# ComputeCalculator.net
KiCad netlist of a schematic drawn in EAGLE
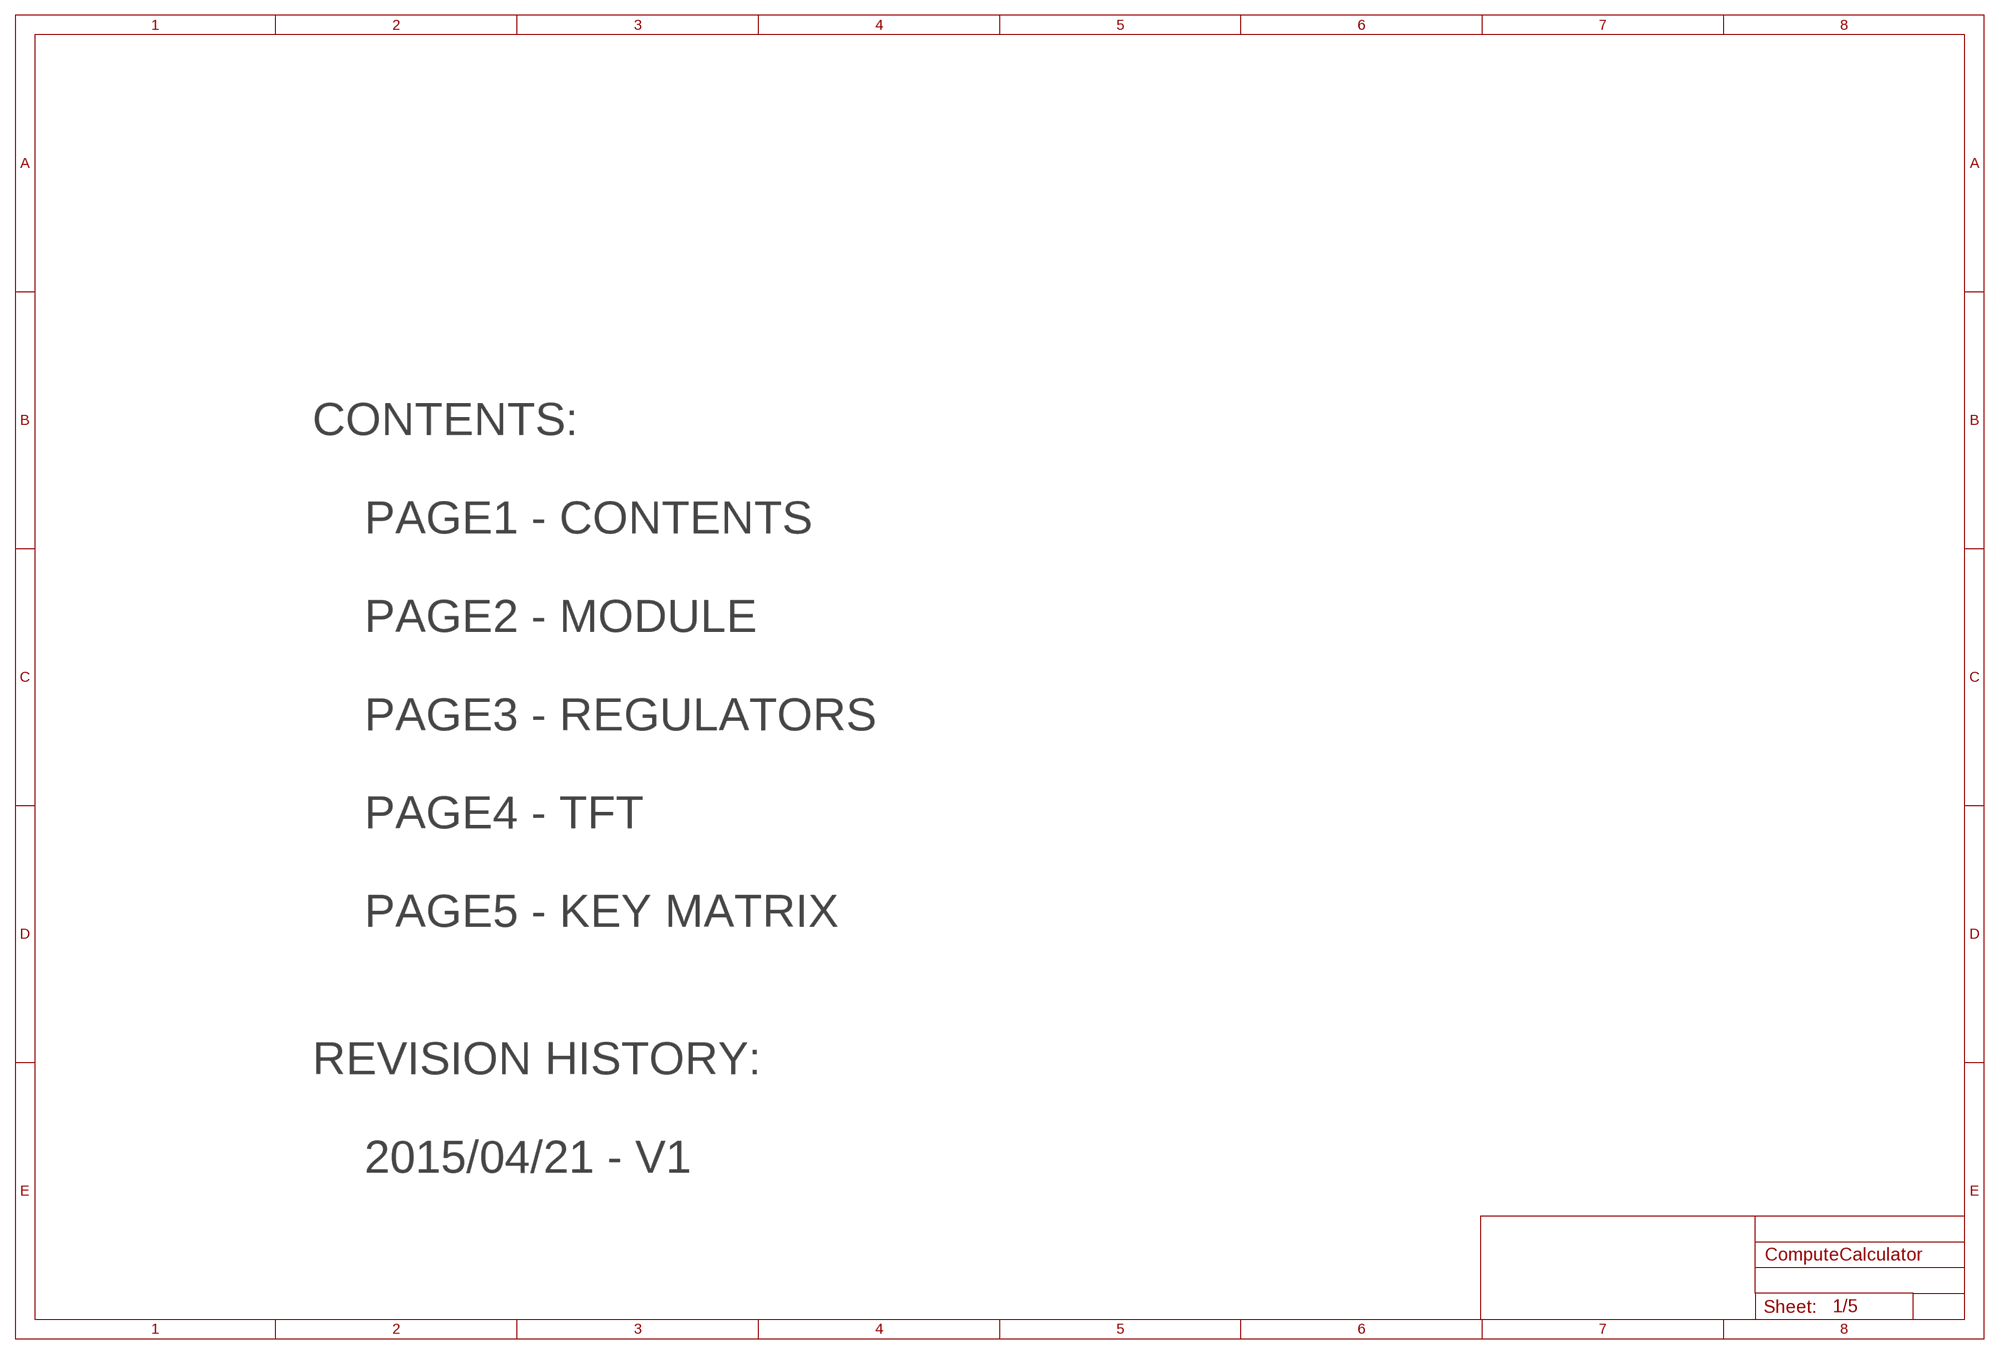
[diagram p0: schematic, sheet 1]
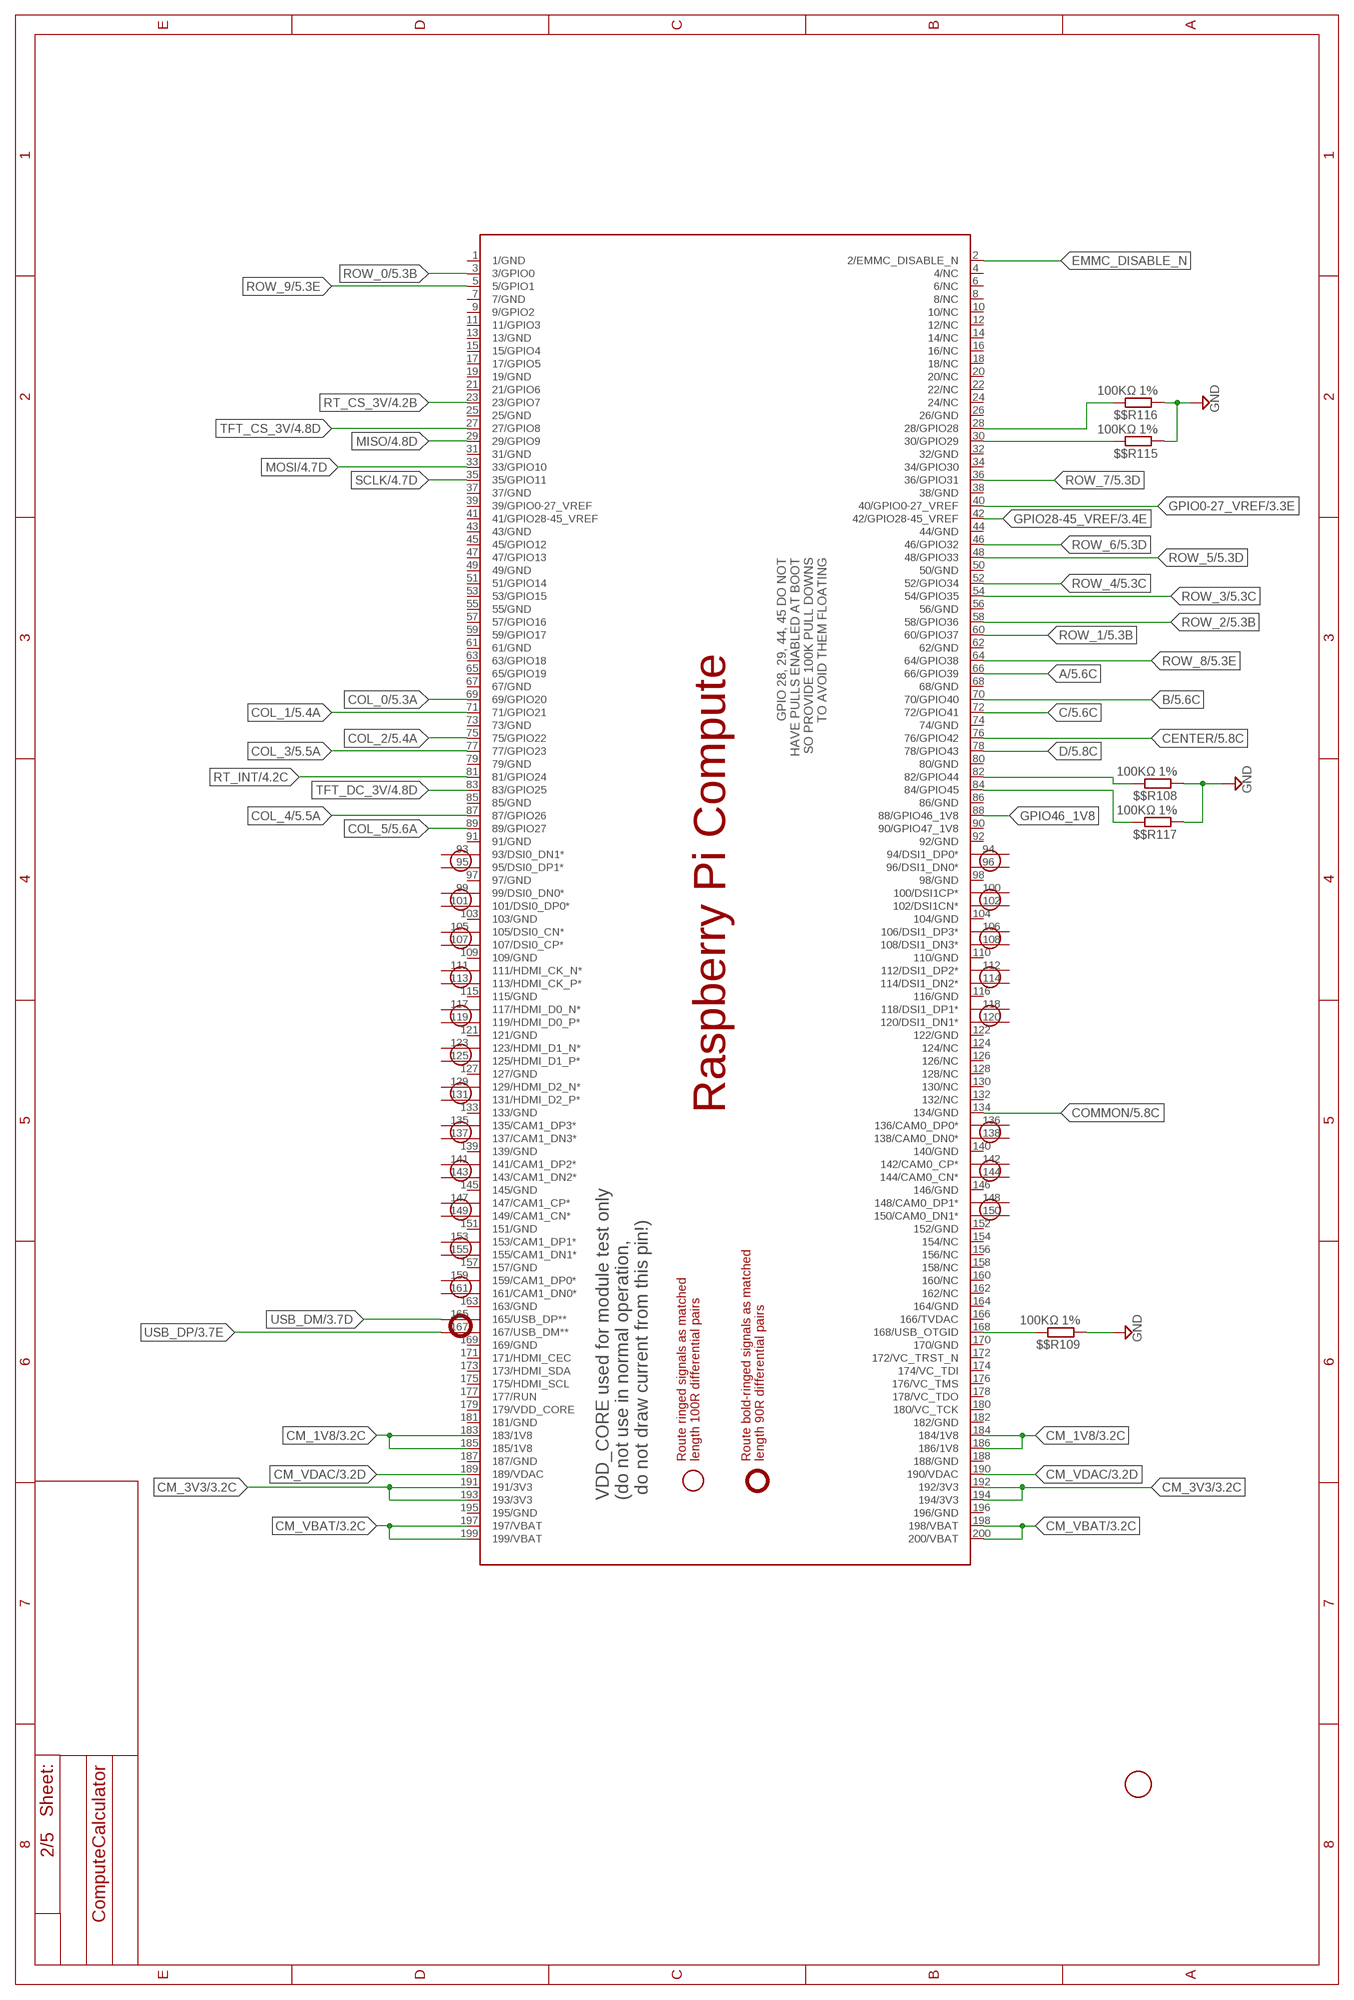
[diagram p1: schematic, sheet 2]
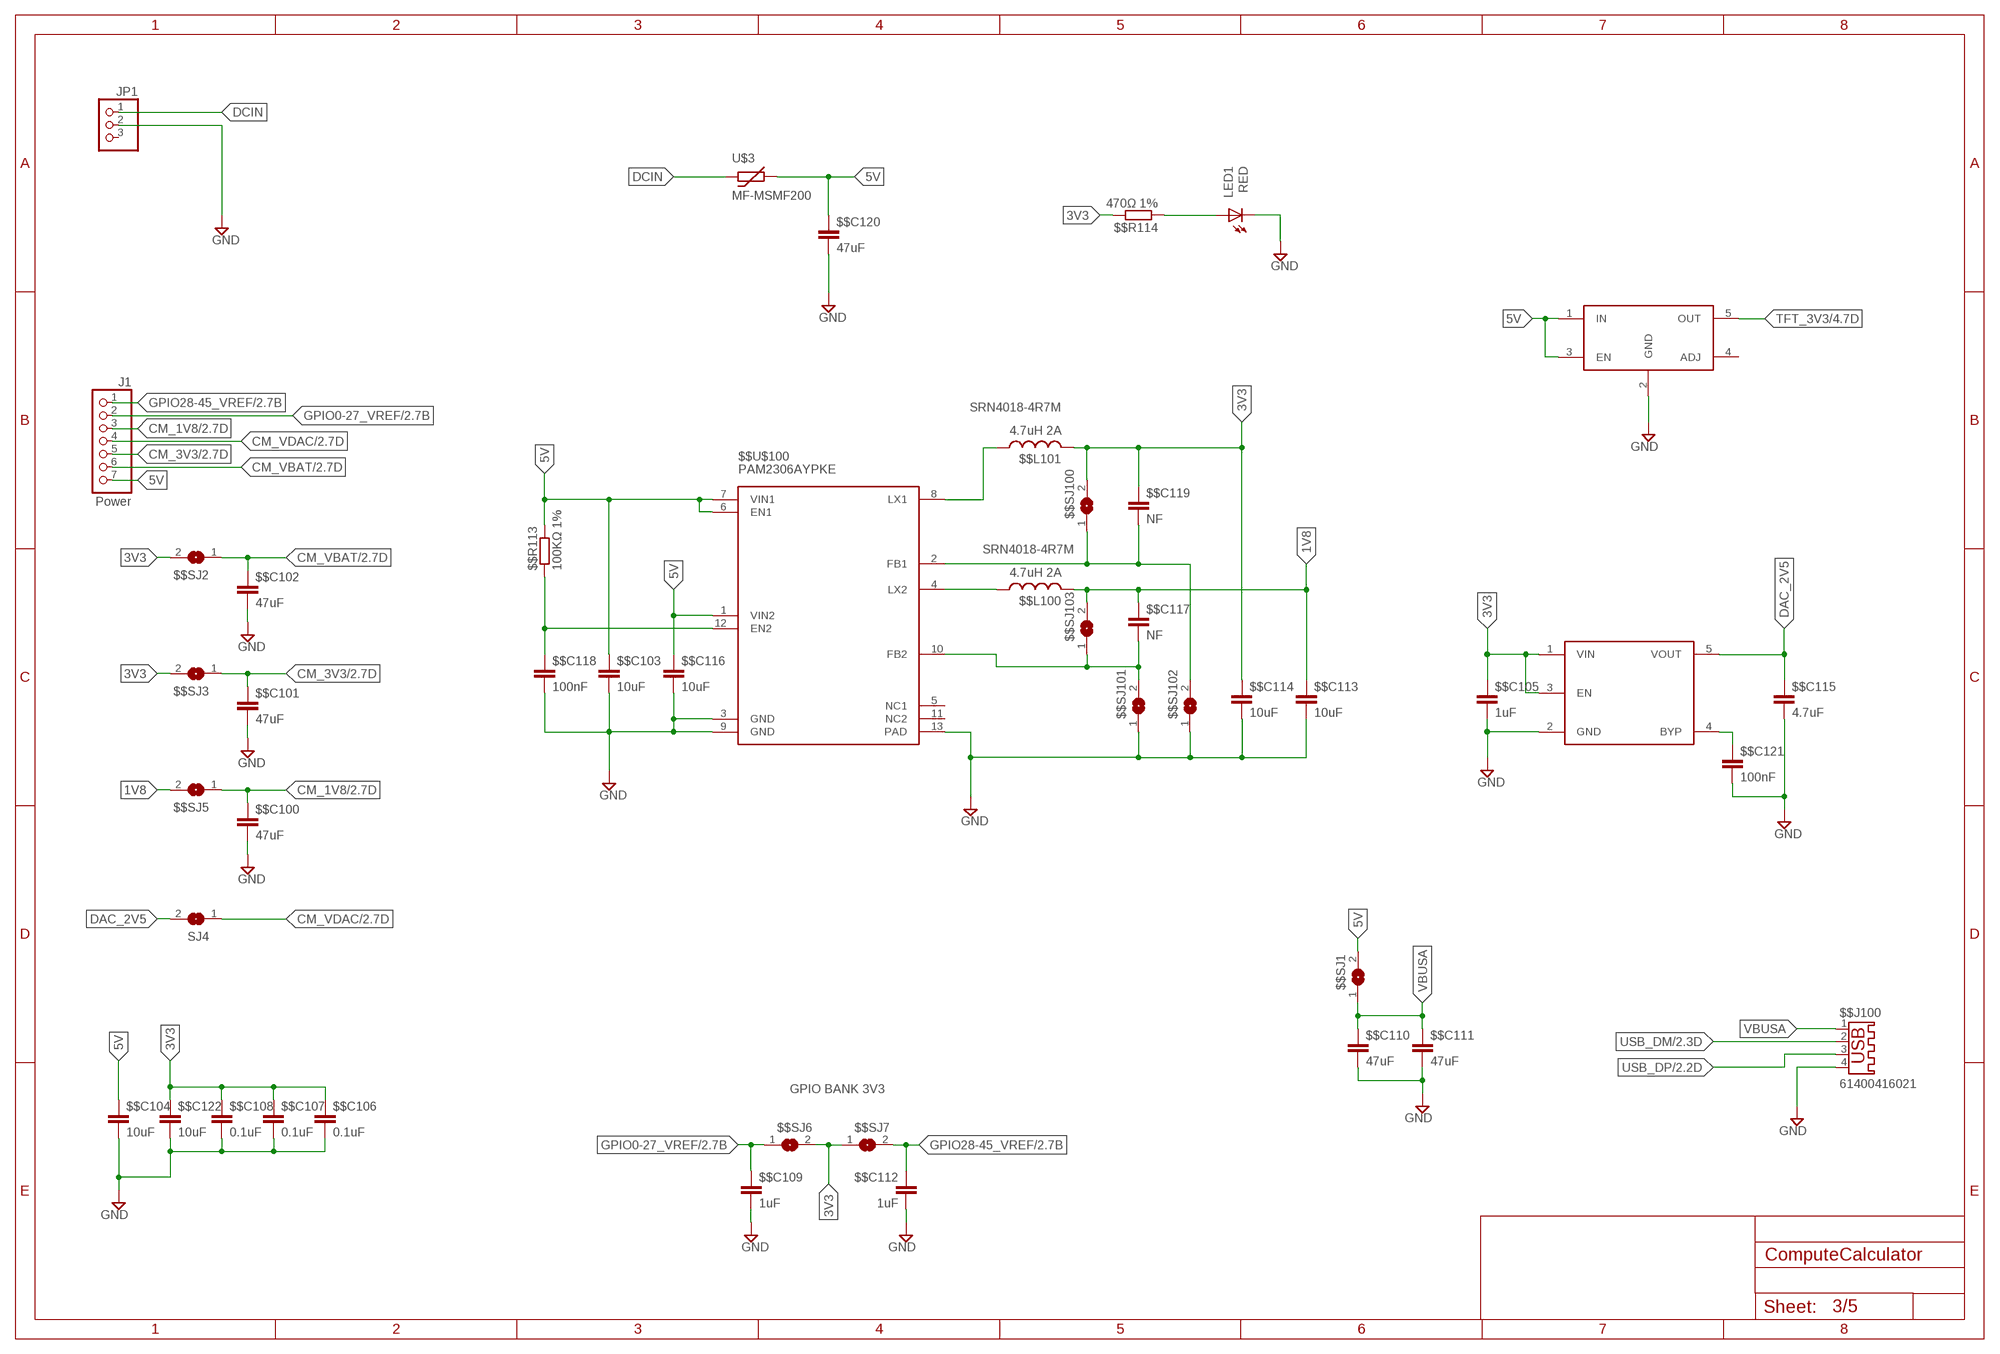
[diagram p2: schematic, sheet 3]
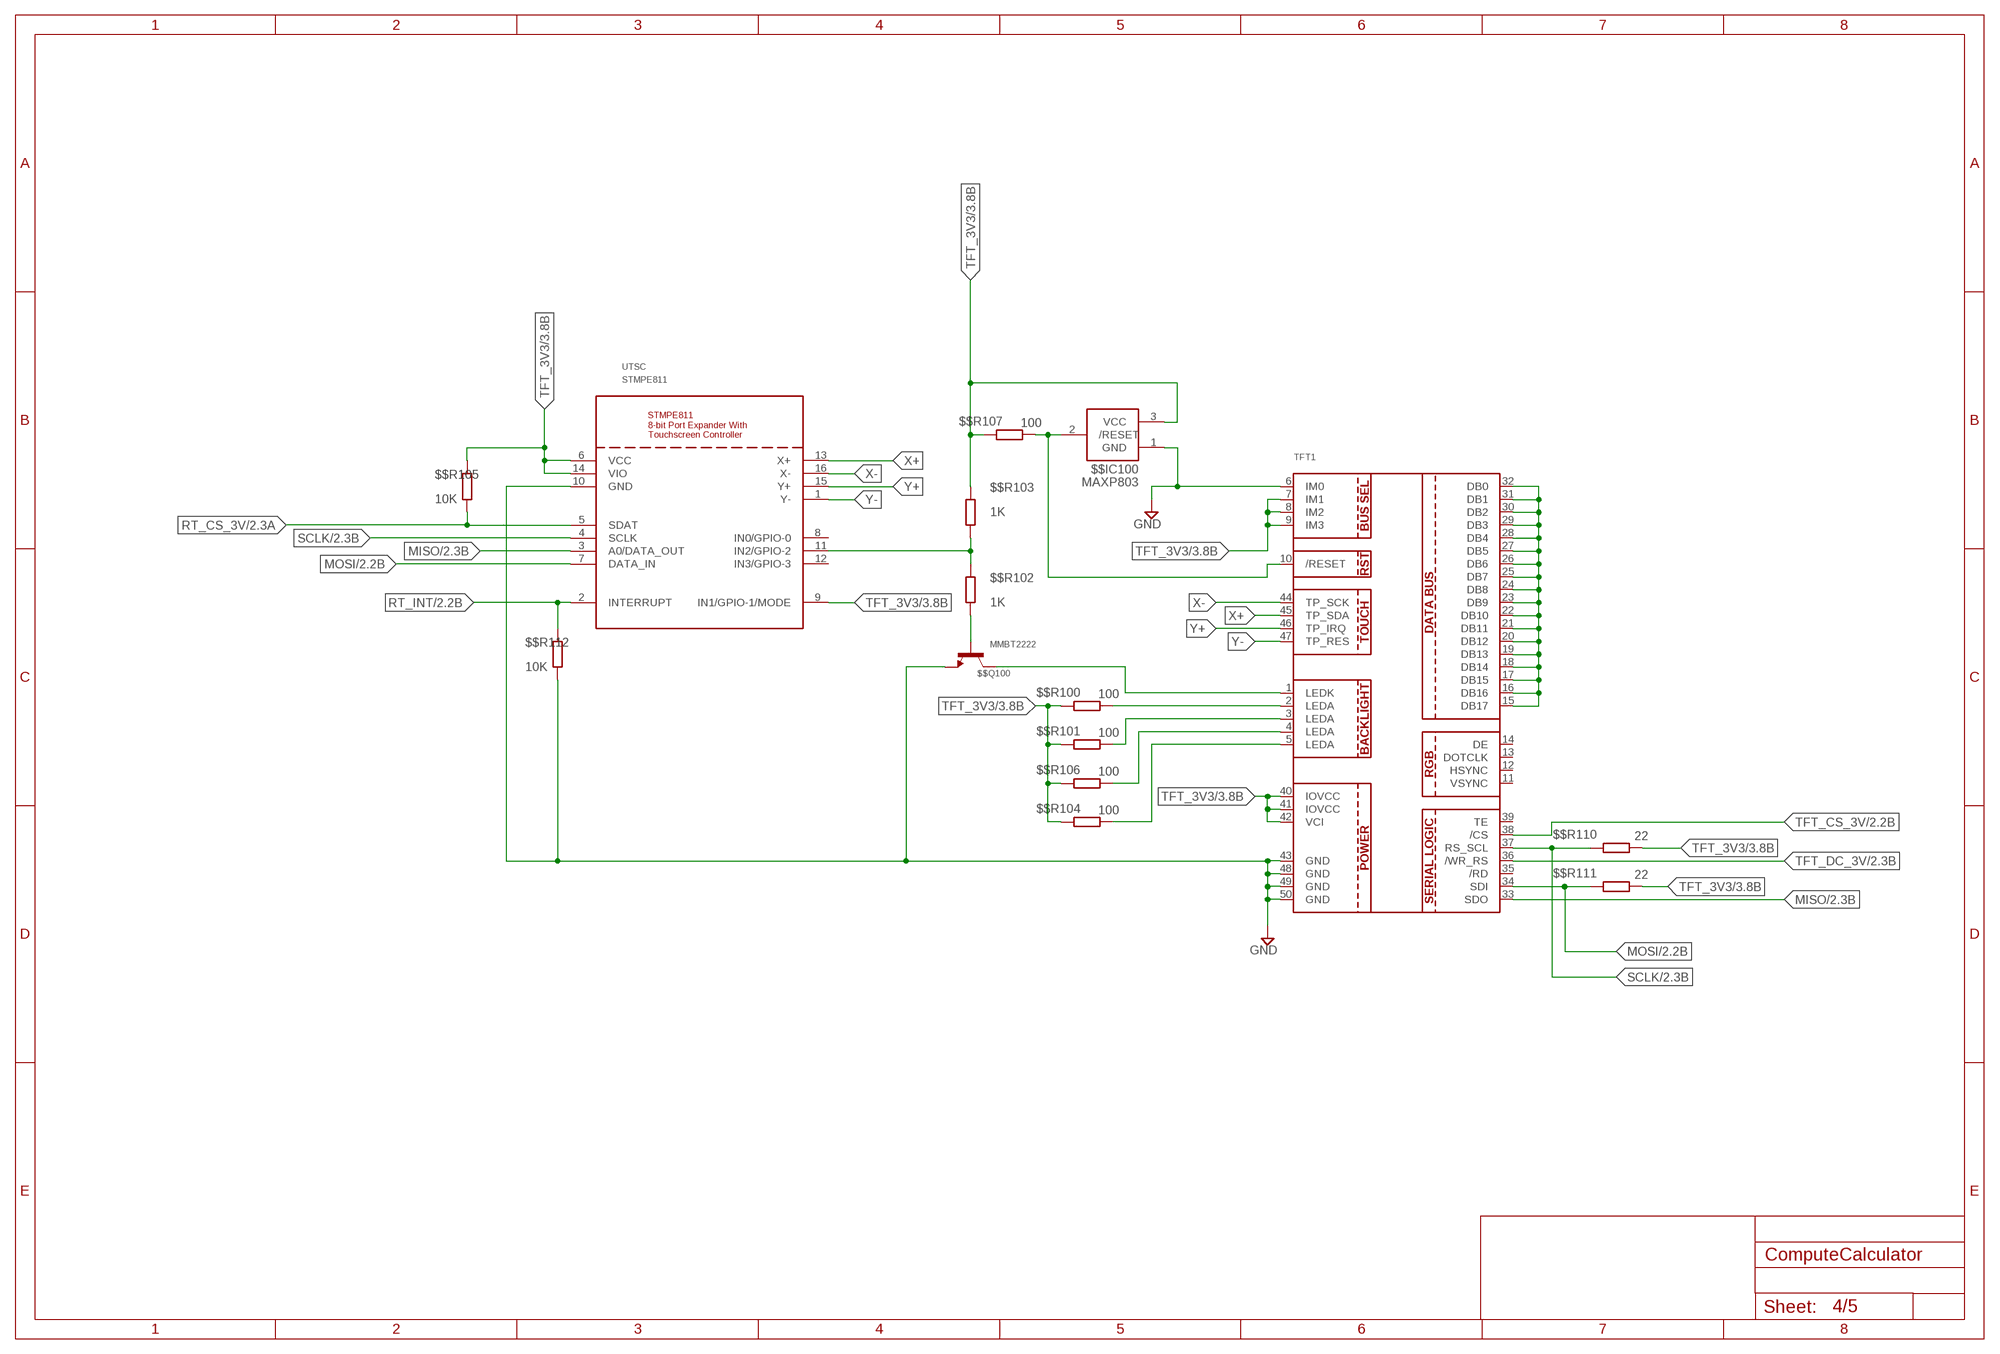
[diagram p3: schematic, sheet 4]
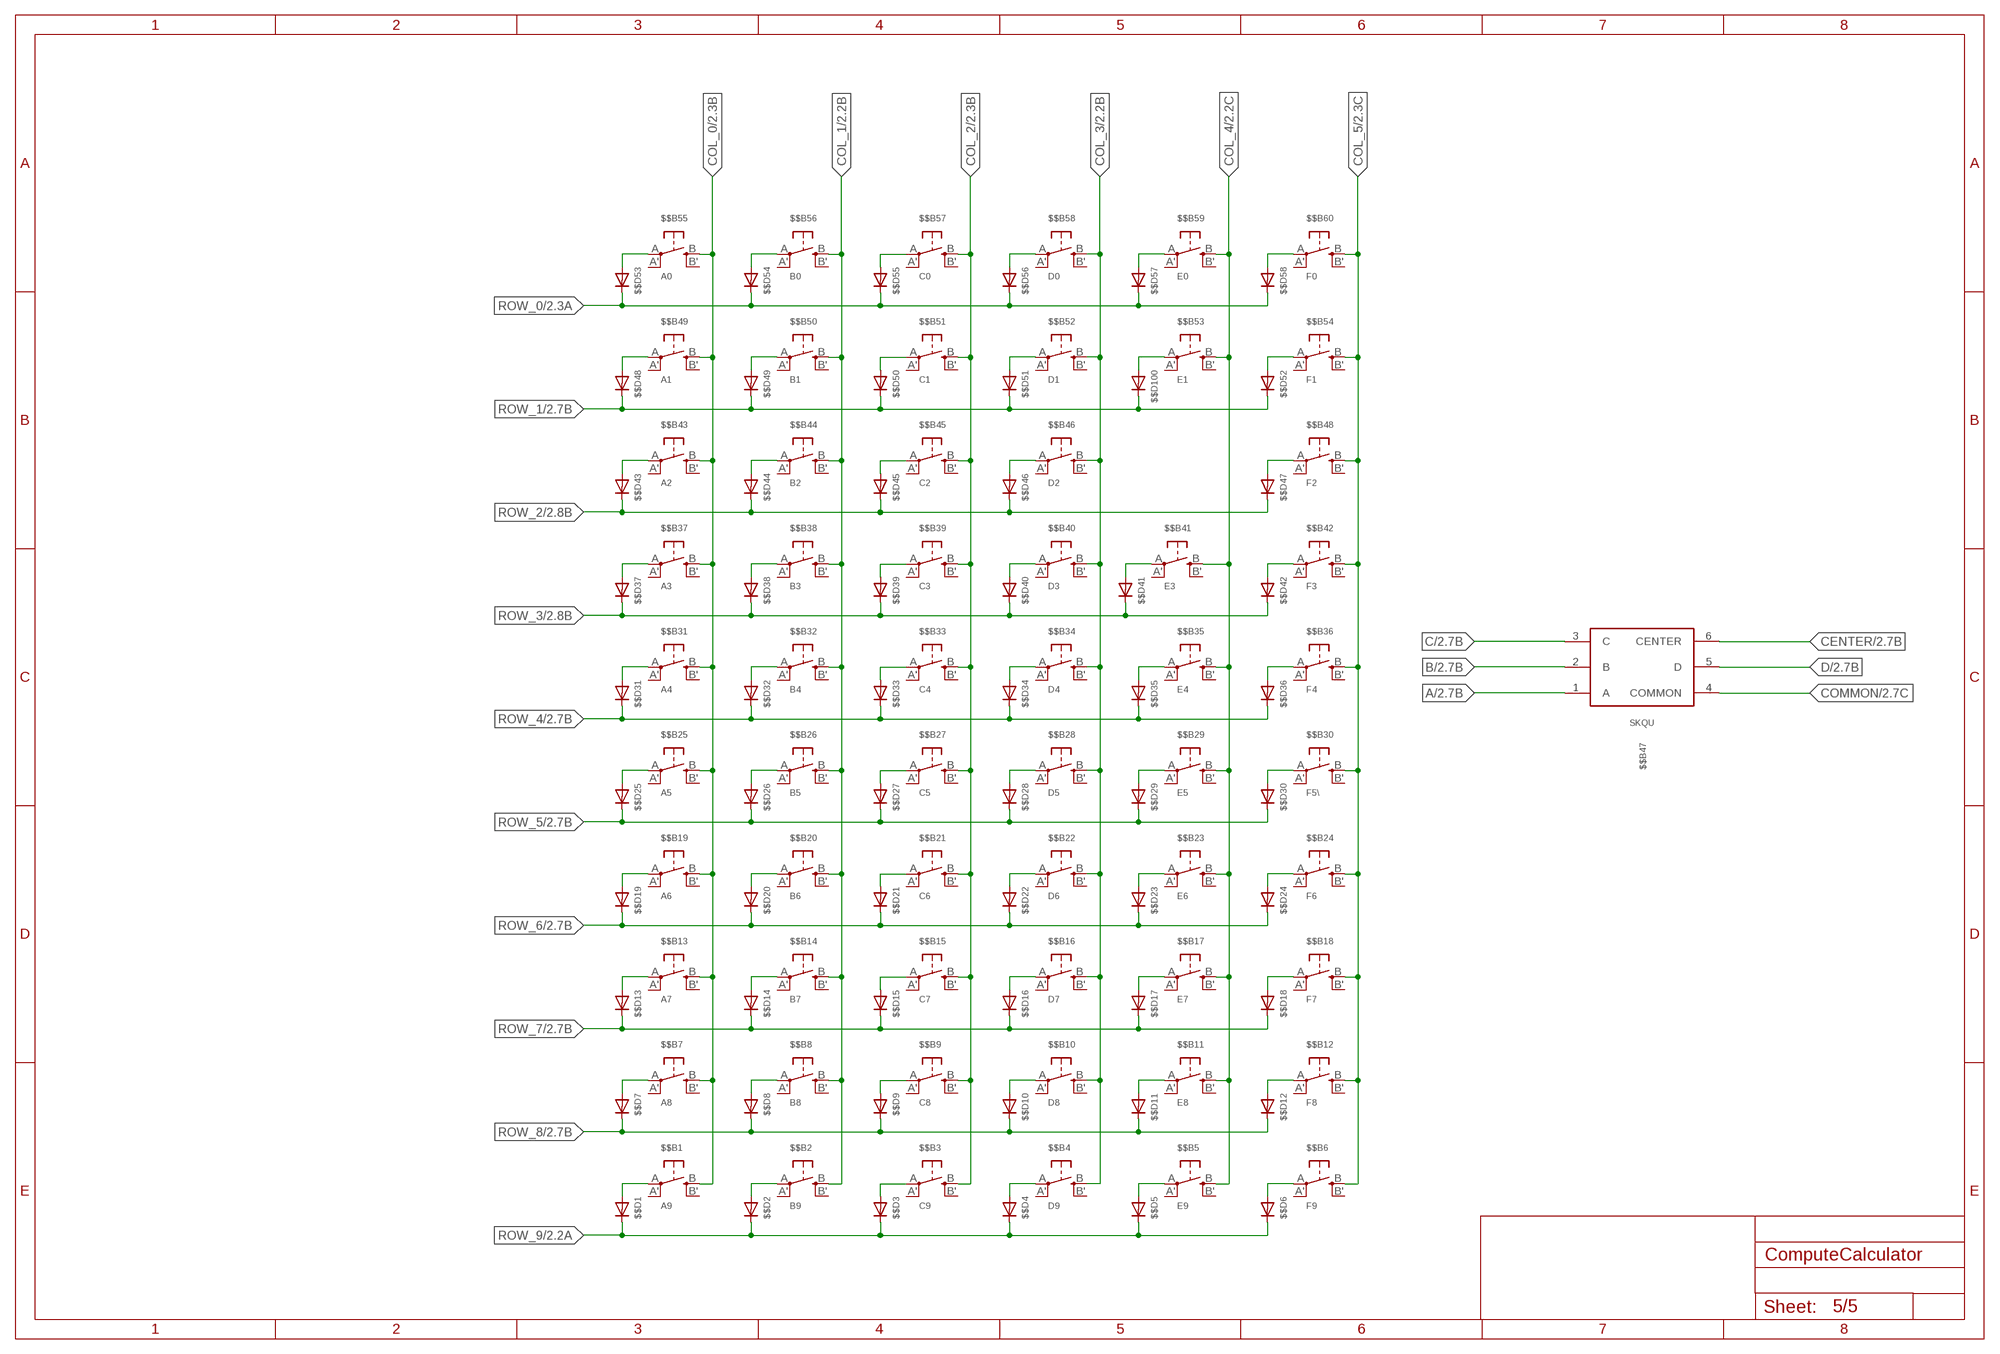
[diagram p4: schematic, sheet 5]

(export (version "E")
  (design (tool "Eeschema 10.0.6"))
  (components
    (comp (ref "$$PCB100")
      (value "RPI_COMPUTE")
      (footprint "eagle-import:RPI_COMPUTE")
      (libsource (lib "eagle-import") (part "RPI_COMPUTE"))
    )
    (comp (ref "$$R108")
      (value "100KΩ 1%")
      (footprint "eagle-import:M1206")
      (libsource (lib "eagle-import") (part "R-EU_M1206"))
    )
    (comp (ref "$$R109")
      (value "100KΩ 1%")
      (footprint "eagle-import:M1206")
      (libsource (lib "eagle-import") (part "R-EU_M1206"))
    )
    (comp (ref "$$R115")
      (value "100KΩ 1%")
      (footprint "eagle-import:M1206")
      (libsource (lib "eagle-import") (part "R-EU_M1206"))
    )
    (comp (ref "$$R116")
      (value "100KΩ 1%")
      (footprint "eagle-import:M1206")
      (libsource (lib "eagle-import") (part "R-EU_M1206"))
    )
    (comp (ref "$$R117")
      (value "100KΩ 1%")
      (footprint "eagle-import:M1206")
      (libsource (lib "eagle-import") (part "R-EU_M1206"))
    )
    (comp (ref "$$U$1")
      (value "FIDUCIAL")
      (footprint "eagle-import:FIDUCIAL_1MM")
      (libsource (lib "eagle-import") (part "FIDUCIAL"))
    )
    (comp (ref "$$B1")
      (value "A9")
      (footprint "eagle-import:EVQ-Q2")
      (libsource (lib "eagle-import") (part "SWITCH_TACT_SMT"))
    )
    (comp (ref "$$B2")
      (value "B9")
      (footprint "eagle-import:EVQ-Q2")
      (libsource (lib "eagle-import") (part "SWITCH_TACT_SMT"))
    )
    (comp (ref "$$B3")
      (value "C9")
      (footprint "eagle-import:EVQ-Q2")
      (libsource (lib "eagle-import") (part "SWITCH_TACT_SMT"))
    )
    (comp (ref "$$B4")
      (value "D9")
      (footprint "eagle-import:EVQ-Q2")
      (libsource (lib "eagle-import") (part "SWITCH_TACT_SMT"))
    )
    (comp (ref "$$B5")
      (value "E9")
      (footprint "eagle-import:EVQ-Q2")
      (libsource (lib "eagle-import") (part "SWITCH_TACT_SMT"))
    )
    (comp (ref "$$B6")
      (value "F9")
      (footprint "eagle-import:EVQ-Q2")
      (libsource (lib "eagle-import") (part "SWITCH_TACT_SMT"))
    )
    (comp (ref "$$B7")
      (value "A8")
      (footprint "eagle-import:EVQ-Q2")
      (libsource (lib "eagle-import") (part "SWITCH_TACT_SMT"))
    )
    (comp (ref "$$B8")
      (value "B8")
      (footprint "eagle-import:EVQ-Q2")
      (libsource (lib "eagle-import") (part "SWITCH_TACT_SMT"))
    )
    (comp (ref "$$B9")
      (value "C8")
      (footprint "eagle-import:EVQ-Q2")
      (libsource (lib "eagle-import") (part "SWITCH_TACT_SMT"))
    )
    (comp (ref "$$B10")
      (value "D8")
      (footprint "eagle-import:EVQ-Q2")
      (libsource (lib "eagle-import") (part "SWITCH_TACT_SMT"))
    )
    (comp (ref "$$B11")
      (value "E8")
      (footprint "eagle-import:EVQ-Q2")
      (libsource (lib "eagle-import") (part "SWITCH_TACT_SMT"))
    )
    (comp (ref "$$B12")
      (value "F8")
      (footprint "eagle-import:EVQ-Q2")
      (libsource (lib "eagle-import") (part "SWITCH_TACT_SMT"))
    )
    (comp (ref "$$B13")
      (value "A7")
      (footprint "eagle-import:EVQ-Q2")
      (libsource (lib "eagle-import") (part "SWITCH_TACT_SMT"))
    )
    (comp (ref "$$B14")
      (value "B7")
      (footprint "eagle-import:EVQ-Q2")
      (libsource (lib "eagle-import") (part "SWITCH_TACT_SMT"))
    )
    (comp (ref "$$B15")
      (value "C7")
      (footprint "eagle-import:EVQ-Q2")
      (libsource (lib "eagle-import") (part "SWITCH_TACT_SMT"))
    )
    (comp (ref "$$B16")
      (value "D7")
      (footprint "eagle-import:EVQ-Q2")
      (libsource (lib "eagle-import") (part "SWITCH_TACT_SMT"))
    )
    (comp (ref "$$B17")
      (value "E7")
      (footprint "eagle-import:EVQ-Q2")
      (libsource (lib "eagle-import") (part "SWITCH_TACT_SMT"))
    )
    (comp (ref "$$B18")
      (value "F7")
      (footprint "eagle-import:EVQ-Q2")
      (libsource (lib "eagle-import") (part "SWITCH_TACT_SMT"))
    )
    (comp (ref "$$B19")
      (value "A6")
      (footprint "eagle-import:EVQ-Q2")
      (libsource (lib "eagle-import") (part "SWITCH_TACT_SMT"))
    )
    (comp (ref "$$B20")
      (value "B6")
      (footprint "eagle-import:EVQ-Q2")
      (libsource (lib "eagle-import") (part "SWITCH_TACT_SMT"))
    )
    (comp (ref "$$B21")
      (value "C6")
      (footprint "eagle-import:EVQ-Q2")
      (libsource (lib "eagle-import") (part "SWITCH_TACT_SMT"))
    )
    (comp (ref "$$B22")
      (value "D6")
      (footprint "eagle-import:EVQ-Q2")
      (libsource (lib "eagle-import") (part "SWITCH_TACT_SMT"))
    )
    (comp (ref "$$B23")
      (value "E6")
      (footprint "eagle-import:EVQ-Q2")
      (libsource (lib "eagle-import") (part "SWITCH_TACT_SMT"))
    )
    (comp (ref "$$B24")
      (value "F6")
      (footprint "eagle-import:EVQ-Q2")
      (libsource (lib "eagle-import") (part "SWITCH_TACT_SMT"))
    )
    (comp (ref "$$B25")
      (value "A5")
      (footprint "eagle-import:EVQ-Q2")
      (libsource (lib "eagle-import") (part "SWITCH_TACT_SMT"))
    )
    (comp (ref "$$B26")
      (value "B5")
      (footprint "eagle-import:EVQ-Q2")
      (libsource (lib "eagle-import") (part "SWITCH_TACT_SMT"))
    )
    (comp (ref "$$B27")
      (value "C5")
      (footprint "eagle-import:EVQ-Q2")
      (libsource (lib "eagle-import") (part "SWITCH_TACT_SMT"))
    )
    (comp (ref "$$B28")
      (value "D5")
      (footprint "eagle-import:EVQ-Q2")
      (libsource (lib "eagle-import") (part "SWITCH_TACT_SMT"))
    )
    (comp (ref "$$B29")
      (value "E5")
      (footprint "eagle-import:EVQ-Q2")
      (libsource (lib "eagle-import") (part "SWITCH_TACT_SMT"))
    )
    (comp (ref "$$B30")
      (value "F5\\")
      (footprint "eagle-import:EVQ-Q2")
      (libsource (lib "eagle-import") (part "SWITCH_TACT_SMT"))
    )
    (comp (ref "$$B31")
      (value "A4")
      (footprint "eagle-import:EVQ-Q2")
      (libsource (lib "eagle-import") (part "SWITCH_TACT_SMT"))
    )
    (comp (ref "$$B32")
      (value "B4")
      (footprint "eagle-import:EVQ-Q2")
      (libsource (lib "eagle-import") (part "SWITCH_TACT_SMT"))
    )
    (comp (ref "$$B33")
      (value "C4")
      (footprint "eagle-import:EVQ-Q2")
      (libsource (lib "eagle-import") (part "SWITCH_TACT_SMT"))
    )
    (comp (ref "$$B34")
      (value "D4")
      (footprint "eagle-import:EVQ-Q2")
      (libsource (lib "eagle-import") (part "SWITCH_TACT_SMT"))
    )
    (comp (ref "$$B35")
      (value "E4")
      (footprint "eagle-import:EVQ-Q2")
      (libsource (lib "eagle-import") (part "SWITCH_TACT_SMT"))
    )
    (comp (ref "$$B36")
      (value "F4")
      (footprint "eagle-import:EVQ-Q2")
      (libsource (lib "eagle-import") (part "SWITCH_TACT_SMT"))
    )
    (comp (ref "$$B37")
      (value "A3")
      (footprint "eagle-import:EVQ-Q2")
      (libsource (lib "eagle-import") (part "SWITCH_TACT_SMT"))
    )
    (comp (ref "$$B38")
      (value "B3")
      (footprint "eagle-import:EVQ-Q2")
      (libsource (lib "eagle-import") (part "SWITCH_TACT_SMT"))
    )
    (comp (ref "$$B39")
      (value "C3")
      (footprint "eagle-import:EVQ-Q2")
      (libsource (lib "eagle-import") (part "SWITCH_TACT_SMT"))
    )
    (comp (ref "$$B40")
      (value "D3")
      (footprint "eagle-import:EVQ-Q2")
      (libsource (lib "eagle-import") (part "SWITCH_TACT_SMT"))
    )
    (comp (ref "$$B41")
      (value "E3")
      (footprint "eagle-import:EVQ-Q2")
      (libsource (lib "eagle-import") (part "SWITCH_TACT_SMT"))
    )
    (comp (ref "$$B42")
      (value "F3")
      (footprint "eagle-import:EVQ-Q2")
      (libsource (lib "eagle-import") (part "SWITCH_TACT_SMT"))
    )
    (comp (ref "$$B43")
      (value "A2")
      (footprint "eagle-import:EVQ-Q2")
      (libsource (lib "eagle-import") (part "SWITCH_TACT_SMT"))
    )
    (comp (ref "$$B44")
      (value "B2")
      (footprint "eagle-import:EVQ-Q2")
      (libsource (lib "eagle-import") (part "SWITCH_TACT_SMT"))
    )
    (comp (ref "$$B45")
      (value "C2")
      (footprint "eagle-import:EVQ-Q2")
      (libsource (lib "eagle-import") (part "SWITCH_TACT_SMT"))
    )
    (comp (ref "$$B46")
      (value "D2")
      (footprint "eagle-import:EVQ-Q2")
      (libsource (lib "eagle-import") (part "SWITCH_TACT_SMT"))
    )
    (comp (ref "$$B47")
      (value "SKQU")
      (footprint "eagle-import:SKQU")
      (libsource (lib "eagle-import") (part "SKQU"))
    )
    (comp (ref "$$B48")
      (value "F2")
      (footprint "eagle-import:EVQ-Q2")
      (libsource (lib "eagle-import") (part "SWITCH_TACT_SMT"))
    )
    (comp (ref "$$B49")
      (value "A1")
      (footprint "eagle-import:EVQ-Q2")
      (libsource (lib "eagle-import") (part "SWITCH_TACT_SMT"))
    )
    (comp (ref "$$B50")
      (value "B1")
      (footprint "eagle-import:EVQ-Q2")
      (libsource (lib "eagle-import") (part "SWITCH_TACT_SMT"))
    )
    (comp (ref "$$B51")
      (value "C1")
      (footprint "eagle-import:EVQ-Q2")
      (libsource (lib "eagle-import") (part "SWITCH_TACT_SMT"))
    )
    (comp (ref "$$B52")
      (value "D1")
      (footprint "eagle-import:EVQ-Q2")
      (libsource (lib "eagle-import") (part "SWITCH_TACT_SMT"))
    )
    (comp (ref "$$B53")
      (value "E1")
      (footprint "eagle-import:EVQ-Q2")
      (libsource (lib "eagle-import") (part "SWITCH_TACT_SMT"))
    )
    (comp (ref "$$B54")
      (value "F1")
      (footprint "eagle-import:EVQ-Q2")
      (libsource (lib "eagle-import") (part "SWITCH_TACT_SMT"))
    )
    (comp (ref "$$B55")
      (value "A0")
      (footprint "eagle-import:EVQ-Q2")
      (libsource (lib "eagle-import") (part "SWITCH_TACT_SMT"))
    )
    (comp (ref "$$B56")
      (value "B0")
      (footprint "eagle-import:EVQ-Q2")
      (libsource (lib "eagle-import") (part "SWITCH_TACT_SMT"))
    )
    (comp (ref "$$B57")
      (value "C0")
      (footprint "eagle-import:EVQ-Q2")
      (libsource (lib "eagle-import") (part "SWITCH_TACT_SMT"))
    )
    (comp (ref "$$B58")
      (value "D0")
      (footprint "eagle-import:EVQ-Q2")
      (libsource (lib "eagle-import") (part "SWITCH_TACT_SMT"))
    )
    (comp (ref "$$B59")
      (value "E0")
      (footprint "eagle-import:EVQ-Q2")
      (libsource (lib "eagle-import") (part "SWITCH_TACT_SMT"))
    )
    (comp (ref "$$B60")
      (value "F0")
      (footprint "eagle-import:EVQ-Q2")
      (libsource (lib "eagle-import") (part "SWITCH_TACT_SMT"))
    )
    (comp (ref "$$D1")
      (value "DIODESMA")
      (footprint "eagle-import:SMADIODE")
      (libsource (lib "eagle-import") (part "DIODESMA"))
    )
    (comp (ref "$$D2")
      (value "DIODESMA")
      (footprint "eagle-import:SMADIODE")
      (libsource (lib "eagle-import") (part "DIODESMA"))
    )
    (comp (ref "$$D3")
      (value "DIODESMA")
      (footprint "eagle-import:SMADIODE")
      (libsource (lib "eagle-import") (part "DIODESMA"))
    )
    (comp (ref "$$D4")
      (value "DIODESMA")
      (footprint "eagle-import:SMADIODE")
      (libsource (lib "eagle-import") (part "DIODESMA"))
    )
    (comp (ref "$$D5")
      (value "DIODESMA")
      (footprint "eagle-import:SMADIODE")
      (libsource (lib "eagle-import") (part "DIODESMA"))
    )
    (comp (ref "$$D6")
      (value "DIODESMA")
      (footprint "eagle-import:SMADIODE")
      (libsource (lib "eagle-import") (part "DIODESMA"))
    )
    (comp (ref "$$D7")
      (value "DIODESMA")
      (footprint "eagle-import:SMADIODE")
      (libsource (lib "eagle-import") (part "DIODESMA"))
    )
    (comp (ref "$$D8")
      (value "DIODESMA")
      (footprint "eagle-import:SMADIODE")
      (libsource (lib "eagle-import") (part "DIODESMA"))
    )
    (comp (ref "$$D9")
      (value "DIODESMA")
      (footprint "eagle-import:SMADIODE")
      (libsource (lib "eagle-import") (part "DIODESMA"))
    )
    (comp (ref "$$D10")
      (value "DIODESMA")
      (footprint "eagle-import:SMADIODE")
      (libsource (lib "eagle-import") (part "DIODESMA"))
    )
    (comp (ref "$$D11")
      (value "DIODESMA")
      (footprint "eagle-import:SMADIODE")
      (libsource (lib "eagle-import") (part "DIODESMA"))
    )
    (comp (ref "$$D12")
      (value "DIODESMA")
      (footprint "eagle-import:SMADIODE")
      (libsource (lib "eagle-import") (part "DIODESMA"))
    )
    (comp (ref "$$D13")
      (value "DIODESMA")
      (footprint "eagle-import:SMADIODE")
      (libsource (lib "eagle-import") (part "DIODESMA"))
    )
    (comp (ref "$$D14")
      (value "DIODESMA")
      (footprint "eagle-import:SMADIODE")
      (libsource (lib "eagle-import") (part "DIODESMA"))
    )
    (comp (ref "$$D15")
      (value "DIODESMA")
      (footprint "eagle-import:SMADIODE")
      (libsource (lib "eagle-import") (part "DIODESMA"))
    )
    (comp (ref "$$D16")
      (value "DIODESMA")
      (footprint "eagle-import:SMADIODE")
      (libsource (lib "eagle-import") (part "DIODESMA"))
    )
    (comp (ref "$$D17")
      (value "DIODESMA")
      (footprint "eagle-import:SMADIODE")
      (libsource (lib "eagle-import") (part "DIODESMA"))
    )
    (comp (ref "$$D18")
      (value "DIODESMA")
      (footprint "eagle-import:SMADIODE")
      (libsource (lib "eagle-import") (part "DIODESMA"))
    )
    (comp (ref "$$D19")
      (value "DIODESMA")
      (footprint "eagle-import:SMADIODE")
      (libsource (lib "eagle-import") (part "DIODESMA"))
    )
    (comp (ref "$$D20")
      (value "DIODESMA")
      (footprint "eagle-import:SMADIODE")
      (libsource (lib "eagle-import") (part "DIODESMA"))
    )
    (comp (ref "$$D21")
      (value "DIODESMA")
      (footprint "eagle-import:SMADIODE")
      (libsource (lib "eagle-import") (part "DIODESMA"))
    )
    (comp (ref "$$D22")
      (value "DIODESMA")
      (footprint "eagle-import:SMADIODE")
      (libsource (lib "eagle-import") (part "DIODESMA"))
    )
    (comp (ref "$$D23")
      (value "DIODESMA")
      (footprint "eagle-import:SMADIODE")
      (libsource (lib "eagle-import") (part "DIODESMA"))
    )
    (comp (ref "$$D24")
      (value "DIODESMA")
      (footprint "eagle-import:SMADIODE")
      (libsource (lib "eagle-import") (part "DIODESMA"))
    )
    (comp (ref "$$D25")
      (value "DIODESMA")
      (footprint "eagle-import:SMADIODE")
      (libsource (lib "eagle-import") (part "DIODESMA"))
    )
    (comp (ref "$$D26")
      (value "DIODESMA")
      (footprint "eagle-import:SMADIODE")
      (libsource (lib "eagle-import") (part "DIODESMA"))
    )
    (comp (ref "$$D27")
      (value "DIODESMA")
      (footprint "eagle-import:SMADIODE")
      (libsource (lib "eagle-import") (part "DIODESMA"))
    )
    (comp (ref "$$D28")
      (value "DIODESMA")
      (footprint "eagle-import:SMADIODE")
      (libsource (lib "eagle-import") (part "DIODESMA"))
    )
    (comp (ref "$$D29")
      (value "DIODESMA")
      (footprint "eagle-import:SMADIODE")
      (libsource (lib "eagle-import") (part "DIODESMA"))
    )
    (comp (ref "$$D30")
      (value "DIODESMA")
      (footprint "eagle-import:SMADIODE")
      (libsource (lib "eagle-import") (part "DIODESMA"))
    )
    (comp (ref "$$D31")
      (value "DIODESMA")
      (footprint "eagle-import:SMADIODE")
      (libsource (lib "eagle-import") (part "DIODESMA"))
    )
    (comp (ref "$$D32")
      (value "DIODESMA")
      (footprint "eagle-import:SMADIODE")
      (libsource (lib "eagle-import") (part "DIODESMA"))
    )
    (comp (ref "$$D33")
      (value "DIODESMA")
      (footprint "eagle-import:SMADIODE")
      (libsource (lib "eagle-import") (part "DIODESMA"))
    )
    (comp (ref "$$D34")
      (value "DIODESMA")
      (footprint "eagle-import:SMADIODE")
      (libsource (lib "eagle-import") (part "DIODESMA"))
    )
    (comp (ref "$$D35")
      (value "DIODESMA")
      (footprint "eagle-import:SMADIODE")
      (libsource (lib "eagle-import") (part "DIODESMA"))
    )
    (comp (ref "$$D36")
      (value "DIODESMA")
      (footprint "eagle-import:SMADIODE")
      (libsource (lib "eagle-import") (part "DIODESMA"))
    )
    (comp (ref "$$D37")
      (value "DIODESMA")
      (footprint "eagle-import:SMADIODE")
      (libsource (lib "eagle-import") (part "DIODESMA"))
    )
    (comp (ref "$$D38")
      (value "DIODESMA")
      (footprint "eagle-import:SMADIODE")
      (libsource (lib "eagle-import") (part "DIODESMA"))
    )
    (comp (ref "$$D39")
      (value "DIODESMA")
      (footprint "eagle-import:SMADIODE")
      (libsource (lib "eagle-import") (part "DIODESMA"))
    )
    (comp (ref "$$D40")
      (value "DIODESMA")
      (footprint "eagle-import:SMADIODE")
      (libsource (lib "eagle-import") (part "DIODESMA"))
    )
    (comp (ref "$$D41")
      (value "DIODESMA")
      (footprint "eagle-import:SMADIODE")
      (libsource (lib "eagle-import") (part "DIODESMA"))
    )
    (comp (ref "$$D42")
      (value "DIODESMA")
      (footprint "eagle-import:SMADIODE")
      (libsource (lib "eagle-import") (part "DIODESMA"))
    )
    (comp (ref "$$D43")
      (value "DIODESMA")
      (footprint "eagle-import:SMADIODE")
      (libsource (lib "eagle-import") (part "DIODESMA"))
    )
    (comp (ref "$$D44")
      (value "DIODESMA")
      (footprint "eagle-import:SMADIODE")
      (libsource (lib "eagle-import") (part "DIODESMA"))
    )
    (comp (ref "$$D45")
      (value "DIODESMA")
      (footprint "eagle-import:SMADIODE")
      (libsource (lib "eagle-import") (part "DIODESMA"))
    )
    (comp (ref "$$D46")
      (value "DIODESMA")
      (footprint "eagle-import:SMADIODE")
      (libsource (lib "eagle-import") (part "DIODESMA"))
    )
    (comp (ref "$$D47")
      (value "DIODESMA")
      (footprint "eagle-import:SMADIODE")
      (libsource (lib "eagle-import") (part "DIODESMA"))
    )
    (comp (ref "$$D48")
      (value "DIODESMA")
      (footprint "eagle-import:SMADIODE")
      (libsource (lib "eagle-import") (part "DIODESMA"))
    )
    (comp (ref "$$D49")
      (value "DIODESMA")
      (footprint "eagle-import:SMADIODE")
      (libsource (lib "eagle-import") (part "DIODESMA"))
    )
    (comp (ref "$$D50")
      (value "DIODESMA")
      (footprint "eagle-import:SMADIODE")
      (libsource (lib "eagle-import") (part "DIODESMA"))
    )
    (comp (ref "$$D51")
      (value "DIODESMA")
      (footprint "eagle-import:SMADIODE")
      (libsource (lib "eagle-import") (part "DIODESMA"))
    )
    (comp (ref "$$D52")
      (value "DIODESMA")
      (footprint "eagle-import:SMADIODE")
      (libsource (lib "eagle-import") (part "DIODESMA"))
    )
    (comp (ref "$$D53")
      (value "DIODESMA")
      (footprint "eagle-import:SMADIODE")
      (libsource (lib "eagle-import") (part "DIODESMA"))
    )
    (comp (ref "$$D54")
      (value "DIODESMA")
      (footprint "eagle-import:SMADIODE")
      (libsource (lib "eagle-import") (part "DIODESMA"))
    )
    (comp (ref "$$D55")
      (value "DIODESMA")
      (footprint "eagle-import:SMADIODE")
      (libsource (lib "eagle-import") (part "DIODESMA"))
    )
    (comp (ref "$$D56")
      (value "DIODESMA")
      (footprint "eagle-import:SMADIODE")
      (libsource (lib "eagle-import") (part "DIODESMA"))
    )
    (comp (ref "$$D57")
      (value "DIODESMA")
      (footprint "eagle-import:SMADIODE")
      (libsource (lib "eagle-import") (part "DIODESMA"))
    )
    (comp (ref "$$D58")
      (value "DIODESMA")
      (footprint "eagle-import:SMADIODE")
      (libsource (lib "eagle-import") (part "DIODESMA"))
    )
    (comp (ref "$$D100")
      (value "DIODESMA")
      (footprint "eagle-import:SMADIODE")
      (libsource (lib "eagle-import") (part "DIODESMA"))
    )
    (comp (ref "$$IC100")
      (value "MAXP803")
      (footprint "eagle-import:SOT23")
      (libsource (lib "eagle-import") (part "AXP083-SAG"))
    )
    (comp (ref "$$Q100")
      (value "MMBT2222")
      (footprint "eagle-import:SOT23-WIDE")
      (libsource (lib "eagle-import") (part "TRANSISTOR_NPNWIDE"))
    )
    (comp (ref "$$R100")
      (value "100")
      (footprint "eagle-import:M1206")
      (libsource (lib "eagle-import") (part "R-EU_M1206"))
    )
    (comp (ref "$$R101")
      (value "100")
      (footprint "eagle-import:M1206")
      (libsource (lib "eagle-import") (part "R-EU_M1206"))
    )
    (comp (ref "$$R102")
      (value "1K")
      (footprint "eagle-import:M1206")
      (libsource (lib "eagle-import") (part "R-EU_M1206"))
    )
    (comp (ref "$$R103")
      (value "1K")
      (footprint "eagle-import:M1206")
      (libsource (lib "eagle-import") (part "R-EU_M1206"))
    )
    (comp (ref "$$R104")
      (value "100")
      (footprint "eagle-import:M1206")
      (libsource (lib "eagle-import") (part "R-EU_M1206"))
    )
    (comp (ref "$$R105")
      (value "10K")
      (footprint "eagle-import:M1206")
      (libsource (lib "eagle-import") (part "R-EU_M1206"))
    )
    (comp (ref "$$R106")
      (value "100")
      (footprint "eagle-import:M1206")
      (libsource (lib "eagle-import") (part "R-EU_M1206"))
    )
    (comp (ref "$$R107")
      (value "100")
      (footprint "eagle-import:M1206")
      (libsource (lib "eagle-import") (part "R-EU_M1206"))
    )
    (comp (ref "$$R110")
      (value "22")
      (footprint "eagle-import:M1206")
      (libsource (lib "eagle-import") (part "R-EU_M1206"))
    )
    (comp (ref "$$R111")
      (value "22")
      (footprint "eagle-import:M1206")
      (libsource (lib "eagle-import") (part "R-EU_M1206"))
    )
    (comp (ref "$$R112")
      (value "10K")
      (footprint "eagle-import:M1206")
      (libsource (lib "eagle-import") (part "R-EU_M1206"))
    )
    (comp (ref "TFT1")
      (value "DISP_LCD_CTP28_DATASHEET")
      (footprint "eagle-import:TFT_CTP28")
      (libsource (lib "eagle-import") (part "DISP_LCD_CTP28_DATASHEET"))
    )
    (comp (ref "UTSC")
      (value "STMPE811")
      (footprint "eagle-import:QFN16L")
      (libsource (lib "eagle-import") (part "STMPE811"))
    )
    (comp (ref "$$C100")
      (value "47uF")
      (footprint "eagle-import:C1206")
      (libsource (lib "eagle-import") (part "C-EUC1206"))
    )
    (comp (ref "$$C101")
      (value "47uF")
      (footprint "eagle-import:C1206")
      (libsource (lib "eagle-import") (part "C-EUC1206"))
    )
    (comp (ref "$$C102")
      (value "47uF")
      (footprint "eagle-import:C1206")
      (libsource (lib "eagle-import") (part "C-EUC1206"))
    )
    (comp (ref "$$C103")
      (value "10uF")
      (footprint "eagle-import:C1206")
      (libsource (lib "eagle-import") (part "C-EUC1206"))
    )
    (comp (ref "$$C104")
      (value "10uF")
      (footprint "eagle-import:C1206")
      (libsource (lib "eagle-import") (part "C-EUC1206"))
    )
    (comp (ref "$$C105")
      (value "1uF")
      (footprint "eagle-import:C1206")
      (libsource (lib "eagle-import") (part "C-EUC1206"))
    )
    (comp (ref "$$C106")
      (value "0.1uF")
      (footprint "eagle-import:C1206")
      (libsource (lib "eagle-import") (part "C-EUC1206"))
    )
    (comp (ref "$$C107")
      (value "0.1uF")
      (footprint "eagle-import:C1206")
      (libsource (lib "eagle-import") (part "C-EUC1206"))
    )
    (comp (ref "$$C108")
      (value "0.1uF")
      (footprint "eagle-import:C1206")
      (libsource (lib "eagle-import") (part "C-EUC1206"))
    )
    (comp (ref "$$C109")
      (value "1uF")
      (footprint "eagle-import:C1206")
      (libsource (lib "eagle-import") (part "C-EUC1206"))
    )
    (comp (ref "$$C110")
      (value "47uF")
      (footprint "eagle-import:C1206")
      (libsource (lib "eagle-import") (part "C-EUC1206"))
    )
    (comp (ref "$$C111")
      (value "47uF")
      (footprint "eagle-import:C1206")
      (libsource (lib "eagle-import") (part "C-EUC1206"))
    )
    (comp (ref "$$C112")
      (value "1uF")
      (footprint "eagle-import:C1206")
      (libsource (lib "eagle-import") (part "C-EUC1206"))
    )
    (comp (ref "$$C113")
      (value "10uF")
      (footprint "eagle-import:C1206")
      (libsource (lib "eagle-import") (part "C-EUC1206"))
    )
    (comp (ref "$$C114")
      (value "10uF")
      (footprint "eagle-import:C1206")
      (libsource (lib "eagle-import") (part "C-EUC1206"))
    )
    (comp (ref "$$C115")
      (value "4.7uF")
      (footprint "eagle-import:C1206")
      (libsource (lib "eagle-import") (part "C-EUC1206"))
    )
    (comp (ref "$$C116")
      (value "10uF")
      (footprint "eagle-import:C1206")
      (libsource (lib "eagle-import") (part "C-EUC1206"))
    )
    (comp (ref "$$C117")
      (value "NF")
      (footprint "eagle-import:C1206")
      (libsource (lib "eagle-import") (part "C-EUC1206"))
    )
    (comp (ref "$$C118")
      (value "100nF")
      (footprint "eagle-import:C1206")
      (libsource (lib "eagle-import") (part "C-EUC1206"))
    )
    (comp (ref "$$C119")
      (value "NF")
      (footprint "eagle-import:C1206")
      (libsource (lib "eagle-import") (part "C-EUC1206"))
    )
    (comp (ref "$$C120")
      (value "47uF")
      (footprint "eagle-import:C0603")
      (libsource (lib "eagle-import") (part "CAPACITOR"))
    )
    (comp (ref "$$C121")
      (value "100nF")
      (footprint "eagle-import:C1206")
      (libsource (lib "eagle-import") (part "C-EUC1206"))
    )
    (comp (ref "$$C122")
      (value "10uF")
      (footprint "eagle-import:C1206")
      (libsource (lib "eagle-import") (part "C-EUC1206"))
    )
    (comp (ref "$$J100")
      (value "61400416021")
      (footprint "eagle-import:USB-A003")
      (libsource (lib "eagle-import") (part "USB-A003"))
    )
    (comp (ref "$$L100")
      (value "SRN4018-4R7M")
      (footprint "eagle-import:POWER-CHOKE_WE-TPC")
      (libsource (lib "eagle-import") (part "L-USWE-TPC"))
    )
    (comp (ref "$$L101")
      (value "SRN4018-4R7M")
      (footprint "eagle-import:POWER-CHOKE_WE-TPC")
      (libsource (lib "eagle-import") (part "L-USWE-TPC"))
    )
    (comp (ref "$$R113")
      (value "100KΩ 1%")
      (footprint "eagle-import:M1206")
      (libsource (lib "eagle-import") (part "R-EU_M1206"))
    )
    (comp (ref "$$R114")
      (value "470Ω 1%")
      (footprint "eagle-import:M1206")
      (libsource (lib "eagle-import") (part "R-EU_M1206"))
    )
    (comp (ref "$$SJ1")
      (value "JUMPER")
      (footprint "eagle-import:SJW")
      (libsource (lib "eagle-import") (part "JUMPER"))
    )
    (comp (ref "$$SJ2")
      (value "JUMPER")
      (footprint "eagle-import:SJW")
      (libsource (lib "eagle-import") (part "JUMPER"))
    )
    (comp (ref "$$SJ3")
      (value "JUMPER")
      (footprint "eagle-import:SJW")
      (libsource (lib "eagle-import") (part "JUMPER"))
    )
    (comp (ref "$$SJ5")
      (value "JUMPER")
      (footprint "eagle-import:SJW")
      (libsource (lib "eagle-import") (part "JUMPER"))
    )
    (comp (ref "$$SJ6")
      (value "JUMPER")
      (footprint "eagle-import:SJW")
      (libsource (lib "eagle-import") (part "JUMPER"))
    )
    (comp (ref "$$SJ7")
      (value "JUMPER")
      (footprint "eagle-import:SJW")
      (libsource (lib "eagle-import") (part "JUMPER"))
    )
    (comp (ref "$$SJ100")
      (value "JUMPER")
      (footprint "eagle-import:SJW")
      (libsource (lib "eagle-import") (part "JUMPER"))
    )
    (comp (ref "$$SJ101")
      (value "JUMPER")
      (footprint "eagle-import:SJW")
      (libsource (lib "eagle-import") (part "JUMPER"))
    )
    (comp (ref "$$SJ102")
      (value "JUMPER")
      (footprint "eagle-import:SJW")
      (libsource (lib "eagle-import") (part "JUMPER"))
    )
    (comp (ref "$$SJ103")
      (value "JUMPER")
      (footprint "eagle-import:SJW")
      (libsource (lib "eagle-import") (part "JUMPER"))
    )
    (comp (ref "$$U$100")
      (value "PAM2306AYPKE")
      (footprint "eagle-import:WDFN_12L")
      (libsource (lib "eagle-import") (part "PAM2306AYPKE"))
    )
    (comp (ref "$$U$101")
      (value "MIC5225")
      (footprint "eagle-import:SOT-25")
      (libsource (lib "eagle-import") (part "MIC5225"))
    )
    (comp (ref "J1")
      (value "Power")
      (footprint "eagle-import:1X7-BIG")
      (libsource (lib "eagle-import") (part "1X7-BIG"))
    )
    (comp (ref "JP1")
      (value "PINHD-1X3")
      (footprint "eagle-import:1X03")
      (libsource (lib "eagle-import") (part "PINHD-1X3"))
    )
    (comp (ref "LED1")
      (value "RED")
      (footprint "eagle-import:CHIP-LED0805")
      (libsource (lib "eagle-import") (part "LEDCHIP-LED0805"))
    )
    (comp (ref "SJ4")
      (value "JUMPER")
      (footprint "eagle-import:SJW")
      (libsource (lib "eagle-import") (part "JUMPER"))
    )
    (comp (ref "U$3")
      (value "MF-MSMF200")
      (footprint "eagle-import:MF-MSMF200")
      (libsource (lib "eagle-import") (part "MF-MSMF200"))
    )
    (comp (ref "U$4")
      (value "AP7115-25SEG")
      (footprint "eagle-import:SOT-25")
      (libsource (lib "eagle-import") (part "AP7115-25SEG"))
    )
  )
  (nets
    (net (code "1") (name "1V8") (class "Default")
      (node (ref "$$C113") (pin "1") (pinfunction "1_1") (pintype "passive"))
      (node (ref "$$C117") (pin "1") (pinfunction "1_1") (pintype "passive"))
      (node (ref "$$L100") (pin "2") (pinfunction "2_2") (pintype "passive"))
      (node (ref "$$SJ103") (pin "2") (pinfunction "2_2") (pintype "passive"))
      (node (ref "$$SJ5") (pin "2") (pinfunction "2_2") (pintype "passive"))
    )
    (net (code "2") (name "3V3") (class "Default")
      (node (ref "$$C105") (pin "1") (pinfunction "1_1") (pintype "passive"))
      (node (ref "$$C106") (pin "1") (pinfunction "1_1") (pintype "passive"))
      (node (ref "$$C107") (pin "1") (pinfunction "1_1") (pintype "passive"))
      (node (ref "$$C108") (pin "1") (pinfunction "1_1") (pintype "passive"))
      (node (ref "$$C114") (pin "1") (pinfunction "1_1") (pintype "passive"))
      (node (ref "$$C119") (pin "1") (pinfunction "1_1") (pintype "passive"))
      (node (ref "$$C122") (pin "1") (pinfunction "1_1") (pintype "passive"))
      (node (ref "$$L101") (pin "2") (pinfunction "2_2") (pintype "passive"))
      (node (ref "$$R114") (pin "2") (pinfunction "2_2") (pintype "passive"))
      (node (ref "$$SJ100") (pin "2") (pinfunction "2_2") (pintype "passive"))
      (node (ref "$$SJ2") (pin "2") (pinfunction "2_2") (pintype "passive"))
      (node (ref "$$SJ3") (pin "2") (pinfunction "2_2") (pintype "passive"))
      (node (ref "$$SJ6") (pin "2") (pinfunction "2_2") (pintype "passive"))
      (node (ref "$$SJ7") (pin "1") (pinfunction "1_1") (pintype "passive"))
      (node (ref "U$4") (pin "1") (pinfunction "VIN_1") (pintype "bidirectional"))
      (node (ref "U$4") (pin "3") (pinfunction "EN_3") (pintype "bidirectional"))
    )
    (net (code "3") (name "5V") (class "Default")
      (node (ref "$$C103") (pin "1") (pinfunction "1_1") (pintype "passive"))
      (node (ref "$$C104") (pin "1") (pinfunction "1_1") (pintype "passive"))
      (node (ref "$$C116") (pin "1") (pinfunction "1_1") (pintype "passive"))
      (node (ref "$$C120") (pin "1") (pinfunction "1_1") (pintype "passive"))
      (node (ref "$$R113") (pin "2") (pinfunction "2_2") (pintype "passive"))
      (node (ref "$$SJ1") (pin "2") (pinfunction "2_2") (pintype "passive"))
      (node (ref "$$U$100") (pin "1") (pinfunction "VIN2_1") (pintype "bidirectional"))
      (node (ref "$$U$100") (pin "6") (pinfunction "EN1_6") (pintype "bidirectional"))
      (node (ref "$$U$100") (pin "7") (pinfunction "VIN1_7") (pintype "bidirectional"))
      (node (ref "$$U$101") (pin "1") (pinfunction "IN_1") (pintype "bidirectional"))
      (node (ref "$$U$101") (pin "3") (pinfunction "EN_3") (pintype "bidirectional"))
      (node (ref "J1") (pin "7") (pinfunction "7_7") (pintype "passive"))
      (node (ref "U$3") (pin "P$2") (pinfunction "2_P$2") (pintype "passive"))
    )
    (net (code "4") (name "A") (class "Default")
      (node (ref "$$B47") (pin "1") (pinfunction "A_1") (pintype "bidirectional"))
      (node (ref "$$PCB100") (pin "66") (pinfunction "66/GPIO39_66") (pintype "bidirectional"))
    )
    (net (code "5") (name "B") (class "Default")
      (node (ref "$$B47") (pin "2") (pinfunction "B_2") (pintype "bidirectional"))
      (node (ref "$$PCB100") (pin "70") (pinfunction "70/GPIO40_70") (pintype "bidirectional"))
    )
    (net (code "6") (name "C") (class "Default")
      (node (ref "$$B47") (pin "3") (pinfunction "C_3") (pintype "bidirectional"))
      (node (ref "$$PCB100") (pin "72") (pinfunction "72/GPIO41_72") (pintype "bidirectional"))
    )
    (net (code "7") (name "CENTER") (class "Default")
      (node (ref "$$B47") (pin "6") (pinfunction "CENTER_6") (pintype "bidirectional"))
      (node (ref "$$PCB100") (pin "76") (pinfunction "76/GPIO42_76") (pintype "bidirectional"))
    )
    (net (code "8") (name "CM_1V8") (class "Default")
      (node (ref "$$C100") (pin "1") (pinfunction "1_1") (pintype "passive"))
      (node (ref "$$PCB100") (pin "183") (pinfunction "183/1V8_183") (pintype "bidirectional"))
      (node (ref "$$PCB100") (pin "184") (pinfunction "184/1V8_184") (pintype "bidirectional"))
      (node (ref "$$PCB100") (pin "185") (pinfunction "185/1V8_185") (pintype "bidirectional"))
      (node (ref "$$PCB100") (pin "186") (pinfunction "186/1V8_186") (pintype "bidirectional"))
      (node (ref "$$SJ5") (pin "1") (pinfunction "1_1") (pintype "passive"))
      (node (ref "J1") (pin "3") (pinfunction "3_3") (pintype "passive"))
    )
    (net (code "9") (name "CM_3V3") (class "Default")
      (node (ref "$$C101") (pin "1") (pinfunction "1_1") (pintype "passive"))
      (node (ref "$$PCB100") (pin "191") (pinfunction "191/3V3_191") (pintype "bidirectional"))
      (node (ref "$$PCB100") (pin "192") (pinfunction "192/3V3_192") (pintype "bidirectional"))
      (node (ref "$$PCB100") (pin "193") (pinfunction "193/3V3_193") (pintype "bidirectional"))
      (node (ref "$$PCB100") (pin "194") (pinfunction "194/3V3_194") (pintype "bidirectional"))
      (node (ref "$$SJ3") (pin "1") (pinfunction "1_1") (pintype "passive"))
      (node (ref "J1") (pin "5") (pinfunction "5_5") (pintype "passive"))
    )
    (net (code "10") (name "CM_VBAT") (class "Default")
      (node (ref "$$C102") (pin "1") (pinfunction "1_1") (pintype "passive"))
      (node (ref "$$PCB100") (pin "197") (pinfunction "197/VBAT_197") (pintype "bidirectional"))
      (node (ref "$$PCB100") (pin "198") (pinfunction "198/VBAT_198") (pintype "bidirectional"))
      (node (ref "$$PCB100") (pin "199") (pinfunction "199/VBAT_199") (pintype "bidirectional"))
      (node (ref "$$PCB100") (pin "200") (pinfunction "200/VBAT_200") (pintype "bidirectional"))
      (node (ref "$$SJ2") (pin "1") (pinfunction "1_1") (pintype "passive"))
      (node (ref "J1") (pin "6") (pinfunction "6_6") (pintype "passive"))
    )
    (net (code "11") (name "CM_VDAC") (class "Default")
      (node (ref "$$PCB100") (pin "189") (pinfunction "189/VDAC_189") (pintype "bidirectional"))
      (node (ref "$$PCB100") (pin "190") (pinfunction "190/VDAC_190") (pintype "bidirectional"))
      (node (ref "J1") (pin "4") (pinfunction "4_4") (pintype "passive"))
      (node (ref "SJ4") (pin "1") (pinfunction "1_1") (pintype "passive"))
    )
    (net (code "12") (name "COL_0") (class "Default")
      (node (ref "$$B1") (pin "B") (pinfunction "S_B") (pintype "passive"))
      (node (ref "$$B13") (pin "B") (pinfunction "S_B") (pintype "passive"))
      (node (ref "$$B19") (pin "B") (pinfunction "S_B") (pintype "passive"))
      (node (ref "$$B25") (pin "B") (pinfunction "S_B") (pintype "passive"))
      (node (ref "$$B31") (pin "B") (pinfunction "S_B") (pintype "passive"))
      (node (ref "$$B37") (pin "B") (pinfunction "S_B") (pintype "passive"))
      (node (ref "$$B43") (pin "B") (pinfunction "S_B") (pintype "passive"))
      (node (ref "$$B49") (pin "B") (pinfunction "S_B") (pintype "passive"))
      (node (ref "$$B55") (pin "B") (pinfunction "S_B") (pintype "passive"))
      (node (ref "$$B7") (pin "B") (pinfunction "S_B") (pintype "passive"))
      (node (ref "$$PCB100") (pin "69") (pinfunction "69/GPIO20_69") (pintype "bidirectional"))
    )
    (net (code "13") (name "COL_1") (class "Default")
      (node (ref "$$B14") (pin "B") (pinfunction "S_B") (pintype "passive"))
      (node (ref "$$B2") (pin "B") (pinfunction "S_B") (pintype "passive"))
      (node (ref "$$B20") (pin "B") (pinfunction "S_B") (pintype "passive"))
      (node (ref "$$B26") (pin "B") (pinfunction "S_B") (pintype "passive"))
      (node (ref "$$B32") (pin "B") (pinfunction "S_B") (pintype "passive"))
      (node (ref "$$B38") (pin "B") (pinfunction "S_B") (pintype "passive"))
      (node (ref "$$B44") (pin "B") (pinfunction "S_B") (pintype "passive"))
      (node (ref "$$B50") (pin "B") (pinfunction "S_B") (pintype "passive"))
      (node (ref "$$B56") (pin "B") (pinfunction "S_B") (pintype "passive"))
      (node (ref "$$B8") (pin "B") (pinfunction "S_B") (pintype "passive"))
      (node (ref "$$PCB100") (pin "71") (pinfunction "71/GPIO21_71") (pintype "bidirectional"))
    )
    (net (code "14") (name "COL_2") (class "Default")
      (node (ref "$$B15") (pin "B") (pinfunction "S_B") (pintype "passive"))
      (node (ref "$$B21") (pin "B") (pinfunction "S_B") (pintype "passive"))
      (node (ref "$$B27") (pin "B") (pinfunction "S_B") (pintype "passive"))
      (node (ref "$$B3") (pin "B") (pinfunction "S_B") (pintype "passive"))
      (node (ref "$$B33") (pin "B") (pinfunction "S_B") (pintype "passive"))
      (node (ref "$$B39") (pin "B") (pinfunction "S_B") (pintype "passive"))
      (node (ref "$$B45") (pin "B") (pinfunction "S_B") (pintype "passive"))
      (node (ref "$$B51") (pin "B") (pinfunction "S_B") (pintype "passive"))
      (node (ref "$$B57") (pin "B") (pinfunction "S_B") (pintype "passive"))
      (node (ref "$$B9") (pin "B") (pinfunction "S_B") (pintype "passive"))
      (node (ref "$$PCB100") (pin "75") (pinfunction "75/GPIO22_75") (pintype "bidirectional"))
    )
    (net (code "15") (name "COL_3") (class "Default")
      (node (ref "$$B10") (pin "B") (pinfunction "S_B") (pintype "passive"))
      (node (ref "$$B16") (pin "B") (pinfunction "S_B") (pintype "passive"))
      (node (ref "$$B22") (pin "B") (pinfunction "S_B") (pintype "passive"))
      (node (ref "$$B28") (pin "B") (pinfunction "S_B") (pintype "passive"))
      (node (ref "$$B34") (pin "B") (pinfunction "S_B") (pintype "passive"))
      (node (ref "$$B4") (pin "B") (pinfunction "S_B") (pintype "passive"))
      (node (ref "$$B40") (pin "B") (pinfunction "S_B") (pintype "passive"))
      (node (ref "$$B46") (pin "B") (pinfunction "S_B") (pintype "passive"))
      (node (ref "$$B52") (pin "B") (pinfunction "S_B") (pintype "passive"))
      (node (ref "$$B58") (pin "B") (pinfunction "S_B") (pintype "passive"))
      (node (ref "$$PCB100") (pin "77") (pinfunction "77/GPIO23_77") (pintype "bidirectional"))
    )
    (net (code "16") (name "COL_4") (class "Default")
      (node (ref "$$B11") (pin "B") (pinfunction "S_B") (pintype "passive"))
      (node (ref "$$B17") (pin "B") (pinfunction "S_B") (pintype "passive"))
      (node (ref "$$B23") (pin "B") (pinfunction "S_B") (pintype "passive"))
      (node (ref "$$B29") (pin "B") (pinfunction "S_B") (pintype "passive"))
      (node (ref "$$B35") (pin "B") (pinfunction "S_B") (pintype "passive"))
      (node (ref "$$B41") (pin "B") (pinfunction "S_B") (pintype "passive"))
      (node (ref "$$B5") (pin "B") (pinfunction "S_B") (pintype "passive"))
      (node (ref "$$B53") (pin "B") (pinfunction "S_B") (pintype "passive"))
      (node (ref "$$B59") (pin "B") (pinfunction "S_B") (pintype "passive"))
      (node (ref "$$PCB100") (pin "87") (pinfunction "87/GPIO26_87") (pintype "bidirectional"))
    )
    (net (code "17") (name "COL_5") (class "Default")
      (node (ref "$$B12") (pin "B") (pinfunction "S_B") (pintype "passive"))
      (node (ref "$$B18") (pin "B") (pinfunction "S_B") (pintype "passive"))
      (node (ref "$$B24") (pin "B") (pinfunction "S_B") (pintype "passive"))
      (node (ref "$$B30") (pin "B") (pinfunction "S_B") (pintype "passive"))
      (node (ref "$$B36") (pin "B") (pinfunction "S_B") (pintype "passive"))
      (node (ref "$$B42") (pin "B") (pinfunction "S_B") (pintype "passive"))
      (node (ref "$$B48") (pin "B") (pinfunction "S_B") (pintype "passive"))
      (node (ref "$$B54") (pin "B") (pinfunction "S_B") (pintype "passive"))
      (node (ref "$$B6") (pin "B") (pinfunction "S_B") (pintype "passive"))
      (node (ref "$$B60") (pin "B") (pinfunction "S_B") (pintype "passive"))
      (node (ref "$$PCB100") (pin "89") (pinfunction "89/GPIO27_89") (pintype "bidirectional"))
    )
    (net (code "18") (name "COMMON") (class "Default")
      (node (ref "$$B47") (pin "4") (pinfunction "COMMON_4") (pintype "bidirectional"))
      (node (ref "$$PCB100") (pin "134") (pinfunction "134/GND_134") (pintype "bidirectional"))
    )
    (net (code "19") (name "D") (class "Default")
      (node (ref "$$B47") (pin "5") (pinfunction "D_5") (pintype "bidirectional"))
      (node (ref "$$PCB100") (pin "78") (pinfunction "78/GPIO43_78") (pintype "bidirectional"))
    )
    (net (code "20") (name "DAC_2V5") (class "Default")
      (node (ref "$$C115") (pin "1") (pinfunction "1_1") (pintype "passive"))
      (node (ref "SJ4") (pin "2") (pinfunction "2_2") (pintype "passive"))
      (node (ref "U$4") (pin "5") (pinfunction "VOUT_5") (pintype "bidirectional"))
    )
    (net (code "21") (name "DCIN") (class "Default")
      (node (ref "JP1") (pin "1") (pinfunction "1_1") (pintype "passive"))
      (node (ref "U$3") (pin "P$1") (pinfunction "1_P$1") (pintype "passive"))
    )
    (net (code "22") (name "EMMC_DISABLE_N") (class "Default")
      (node (ref "$$PCB100") (pin "2") (pinfunction "2/EMMC_DISABLE_N_2") (pintype "bidirectional"))
    )
    (net (code "23") (name "GND") (class "Default")
      (node (ref "$$C100") (pin "2") (pinfunction "2_2") (pintype "passive"))
      (node (ref "$$C101") (pin "2") (pinfunction "2_2") (pintype "passive"))
      (node (ref "$$C102") (pin "2") (pinfunction "2_2") (pintype "passive"))
      (node (ref "$$C103") (pin "2") (pinfunction "2_2") (pintype "passive"))
      (node (ref "$$C104") (pin "2") (pinfunction "2_2") (pintype "passive"))
      (node (ref "$$C105") (pin "2") (pinfunction "2_2") (pintype "passive"))
      (node (ref "$$C106") (pin "2") (pinfunction "2_2") (pintype "passive"))
      (node (ref "$$C107") (pin "2") (pinfunction "2_2") (pintype "passive"))
      (node (ref "$$C108") (pin "2") (pinfunction "2_2") (pintype "passive"))
      (node (ref "$$C109") (pin "2") (pinfunction "2_2") (pintype "passive"))
      (node (ref "$$C110") (pin "2") (pinfunction "2_2") (pintype "passive"))
      (node (ref "$$C111") (pin "2") (pinfunction "2_2") (pintype "passive"))
      (node (ref "$$C112") (pin "2") (pinfunction "2_2") (pintype "passive"))
      (node (ref "$$C113") (pin "2") (pinfunction "2_2") (pintype "passive"))
      (node (ref "$$C114") (pin "2") (pinfunction "2_2") (pintype "passive"))
      (node (ref "$$C115") (pin "2") (pinfunction "2_2") (pintype "passive"))
      (node (ref "$$C116") (pin "2") (pinfunction "2_2") (pintype "passive"))
      (node (ref "$$C118") (pin "2") (pinfunction "2_2") (pintype "passive"))
      (node (ref "$$C120") (pin "2") (pinfunction "2_2") (pintype "passive"))
      (node (ref "$$C121") (pin "2") (pinfunction "2_2") (pintype "passive"))
      (node (ref "$$C122") (pin "2") (pinfunction "2_2") (pintype "passive"))
      (node (ref "$$IC100") (pin "1") (pinfunction "GND_1") (pintype "power_in"))
      (node (ref "$$J100") (pin "4") (pinfunction "4_4") (pintype "passive"))
      (node (ref "$$Q100") (pin "2") (pinfunction "E_2") (pintype "passive"))
      (node (ref "$$R108") (pin "1") (pinfunction "1_1") (pintype "passive"))
      (node (ref "$$R109") (pin "1") (pinfunction "1_1") (pintype "passive"))
      (node (ref "$$R112") (pin "2") (pinfunction "2_2") (pintype "passive"))
      (node (ref "$$R115") (pin "1") (pinfunction "1_1") (pintype "passive"))
      (node (ref "$$R116") (pin "1") (pinfunction "1_1") (pintype "passive"))
      (node (ref "$$R117") (pin "1") (pinfunction "1_1") (pintype "passive"))
      (node (ref "$$SJ101") (pin "1") (pinfunction "1_1") (pintype "passive"))
      (node (ref "$$SJ102") (pin "1") (pinfunction "1_1") (pintype "passive"))
      (node (ref "$$U$100") (pin "13") (pinfunction "PAD_13") (pintype "bidirectional"))
      (node (ref "$$U$100") (pin "3") (pinfunction "GND_3") (pintype "bidirectional"))
      (node (ref "$$U$100") (pin "9") (pinfunction "GND_9") (pintype "bidirectional"))
      (node (ref "$$U$101") (pin "2") (pinfunction "GND_2") (pintype "bidirectional"))
      (node (ref "JP1") (pin "2") (pinfunction "2_2") (pintype "passive"))
      (node (ref "LED1") (pin "C") (pinfunction "C_C") (pintype "passive"))
      (node (ref "TFT1") (pin "43") (pinfunction "GND_43") (pintype "bidirectional"))
      (node (ref "TFT1") (pin "48") (pinfunction "GND_48") (pintype "bidirectional"))
      (node (ref "TFT1") (pin "49") (pinfunction "GND_49") (pintype "bidirectional"))
      (node (ref "TFT1") (pin "50") (pinfunction "GND_50") (pintype "bidirectional"))
      (node (ref "TFT1") (pin "6") (pinfunction "IM0_6") (pintype "bidirectional"))
      (node (ref "U$4") (pin "2") (pinfunction "GND_2") (pintype "bidirectional"))
      (node (ref "UTSC") (pin "10") (pinfunction "GND_10") (pintype "bidirectional"))
    )
    (net (code "24") (name "GPIO0-27_VREF") (class "Default")
      (node (ref "$$C109") (pin "1") (pinfunction "1_1") (pintype "passive"))
      (node (ref "$$PCB100") (pin "40") (pinfunction "40/GPIO0-27_VREF_40") (pintype "bidirectional"))
      (node (ref "$$SJ6") (pin "1") (pinfunction "1_1") (pintype "passive"))
      (node (ref "J1") (pin "2") (pinfunction "2_2") (pintype "passive"))
    )
    (net (code "25") (name "GPIO28-45_VREF") (class "Default")
      (node (ref "$$C112") (pin "1") (pinfunction "1_1") (pintype "passive"))
      (node (ref "$$PCB100") (pin "42") (pinfunction "42/GPIO28-45_VREF_42") (pintype "bidirectional"))
      (node (ref "$$SJ7") (pin "2") (pinfunction "2_2") (pintype "passive"))
      (node (ref "J1") (pin "1") (pinfunction "1_1") (pintype "passive"))
    )
    (net (code "26") (name "GPIO46_1V8") (class "Default")
      (node (ref "$$PCB100") (pin "88") (pinfunction "88/GPIO46_1V8_88") (pintype "bidirectional"))
    )
    (net (code "27") (name "MISO") (class "Default")
      (node (ref "$$PCB100") (pin "29") (pinfunction "29/GPIO9_29") (pintype "bidirectional"))
      (node (ref "TFT1") (pin "33") (pinfunction "SDO_33") (pintype "bidirectional"))
      (node (ref "UTSC") (pin "3") (pinfunction "A0/DATA_OUT_3") (pintype "bidirectional"))
    )
    (net (code "28") (name "MOSI") (class "Default")
      (node (ref "$$PCB100") (pin "33") (pinfunction "33/GPIO10_33") (pintype "bidirectional"))
      (node (ref "$$R111") (pin "2") (pinfunction "2_2") (pintype "passive"))
      (node (ref "TFT1") (pin "34") (pinfunction "SDI_34") (pintype "bidirectional"))
      (node (ref "UTSC") (pin "7") (pinfunction "DATA_IN_7") (pintype "bidirectional"))
    )
    (net (code "29") (name "Net-($$B1-P)") (class "Default")
      (node (ref "$$B1") (pin "A") (pinfunction "P_A") (pintype "passive"))
      (node (ref "$$D1") (pin "A") (pinfunction "A_A") (pintype "passive"))
    )
    (net (code "30") (name "Net-($$B2-P)") (class "Default")
      (node (ref "$$B2") (pin "A") (pinfunction "P_A") (pintype "passive"))
      (node (ref "$$D2") (pin "A") (pinfunction "A_A") (pintype "passive"))
    )
    (net (code "31") (name "Net-($$B3-P)") (class "Default")
      (node (ref "$$B3") (pin "A") (pinfunction "P_A") (pintype "passive"))
      (node (ref "$$D3") (pin "A") (pinfunction "A_A") (pintype "passive"))
    )
    (net (code "32") (name "Net-($$B4-P)") (class "Default")
      (node (ref "$$B4") (pin "A") (pinfunction "P_A") (pintype "passive"))
      (node (ref "$$D4") (pin "A") (pinfunction "A_A") (pintype "passive"))
    )
    (net (code "33") (name "Net-($$B5-P)") (class "Default")
      (node (ref "$$B5") (pin "A") (pinfunction "P_A") (pintype "passive"))
      (node (ref "$$D5") (pin "A") (pinfunction "A_A") (pintype "passive"))
    )
    (net (code "34") (name "Net-($$B6-P)") (class "Default")
      (node (ref "$$B6") (pin "A") (pinfunction "P_A") (pintype "passive"))
      (node (ref "$$D6") (pin "A") (pinfunction "A_A") (pintype "passive"))
    )
    (net (code "35") (name "Net-($$B7-P)") (class "Default")
      (node (ref "$$B7") (pin "A") (pinfunction "P_A") (pintype "passive"))
      (node (ref "$$D7") (pin "A") (pinfunction "A_A") (pintype "passive"))
    )
    (net (code "36") (name "Net-($$B8-P)") (class "Default")
      (node (ref "$$B8") (pin "A") (pinfunction "P_A") (pintype "passive"))
      (node (ref "$$D8") (pin "A") (pinfunction "A_A") (pintype "passive"))
    )
    (net (code "37") (name "Net-($$B9-P)") (class "Default")
      (node (ref "$$B9") (pin "A") (pinfunction "P_A") (pintype "passive"))
      (node (ref "$$D9") (pin "A") (pinfunction "A_A") (pintype "passive"))
    )
    (net (code "38") (name "Net-($$B10-P)") (class "Default")
      (node (ref "$$B10") (pin "A") (pinfunction "P_A") (pintype "passive"))
      (node (ref "$$D10") (pin "A") (pinfunction "A_A") (pintype "passive"))
    )
    (net (code "39") (name "Net-($$B11-P)") (class "Default")
      (node (ref "$$B11") (pin "A") (pinfunction "P_A") (pintype "passive"))
      (node (ref "$$D11") (pin "A") (pinfunction "A_A") (pintype "passive"))
    )
    (net (code "40") (name "Net-($$B12-P)") (class "Default")
      (node (ref "$$B12") (pin "A") (pinfunction "P_A") (pintype "passive"))
      (node (ref "$$D12") (pin "A") (pinfunction "A_A") (pintype "passive"))
    )
    (net (code "41") (name "Net-($$B13-P)") (class "Default")
      (node (ref "$$B13") (pin "A") (pinfunction "P_A") (pintype "passive"))
      (node (ref "$$D13") (pin "A") (pinfunction "A_A") (pintype "passive"))
    )
    (net (code "42") (name "Net-($$B14-P)") (class "Default")
      (node (ref "$$B14") (pin "A") (pinfunction "P_A") (pintype "passive"))
      (node (ref "$$D14") (pin "A") (pinfunction "A_A") (pintype "passive"))
    )
    (net (code "43") (name "Net-($$B15-P)") (class "Default")
      (node (ref "$$B15") (pin "A") (pinfunction "P_A") (pintype "passive"))
      (node (ref "$$D15") (pin "A") (pinfunction "A_A") (pintype "passive"))
    )
    (net (code "44") (name "Net-($$B16-P)") (class "Default")
      (node (ref "$$B16") (pin "A") (pinfunction "P_A") (pintype "passive"))
      (node (ref "$$D16") (pin "A") (pinfunction "A_A") (pintype "passive"))
    )
    (net (code "45") (name "Net-($$B17-P)") (class "Default")
      (node (ref "$$B17") (pin "A") (pinfunction "P_A") (pintype "passive"))
      (node (ref "$$D17") (pin "A") (pinfunction "A_A") (pintype "passive"))
    )
    (net (code "46") (name "Net-($$B18-P)") (class "Default")
      (node (ref "$$B18") (pin "A") (pinfunction "P_A") (pintype "passive"))
      (node (ref "$$D18") (pin "A") (pinfunction "A_A") (pintype "passive"))
    )
    (net (code "47") (name "Net-($$B19-P)") (class "Default")
      (node (ref "$$B19") (pin "A") (pinfunction "P_A") (pintype "passive"))
      (node (ref "$$D19") (pin "A") (pinfunction "A_A") (pintype "passive"))
    )
    (net (code "48") (name "Net-($$B20-P)") (class "Default")
      (node (ref "$$B20") (pin "A") (pinfunction "P_A") (pintype "passive"))
      (node (ref "$$D20") (pin "A") (pinfunction "A_A") (pintype "passive"))
    )
    (net (code "49") (name "Net-($$B21-P)") (class "Default")
      (node (ref "$$B21") (pin "A") (pinfunction "P_A") (pintype "passive"))
      (node (ref "$$D21") (pin "A") (pinfunction "A_A") (pintype "passive"))
    )
    (net (code "50") (name "Net-($$B22-P)") (class "Default")
      (node (ref "$$B22") (pin "A") (pinfunction "P_A") (pintype "passive"))
      (node (ref "$$D22") (pin "A") (pinfunction "A_A") (pintype "passive"))
    )
    (net (code "51") (name "Net-($$B23-P)") (class "Default")
      (node (ref "$$B23") (pin "A") (pinfunction "P_A") (pintype "passive"))
      (node (ref "$$D23") (pin "A") (pinfunction "A_A") (pintype "passive"))
    )
    (net (code "52") (name "Net-($$B24-P)") (class "Default")
      (node (ref "$$B24") (pin "A") (pinfunction "P_A") (pintype "passive"))
      (node (ref "$$D24") (pin "A") (pinfunction "A_A") (pintype "passive"))
    )
    (net (code "53") (name "Net-($$B25-P)") (class "Default")
      (node (ref "$$B25") (pin "A") (pinfunction "P_A") (pintype "passive"))
      (node (ref "$$D25") (pin "A") (pinfunction "A_A") (pintype "passive"))
    )
    (net (code "54") (name "Net-($$B26-P)") (class "Default")
      (node (ref "$$B26") (pin "A") (pinfunction "P_A") (pintype "passive"))
      (node (ref "$$D26") (pin "A") (pinfunction "A_A") (pintype "passive"))
    )
    (net (code "55") (name "Net-($$B27-P)") (class "Default")
      (node (ref "$$B27") (pin "A") (pinfunction "P_A") (pintype "passive"))
      (node (ref "$$D27") (pin "A") (pinfunction "A_A") (pintype "passive"))
    )
    (net (code "56") (name "Net-($$B28-P)") (class "Default")
      (node (ref "$$B28") (pin "A") (pinfunction "P_A") (pintype "passive"))
      (node (ref "$$D28") (pin "A") (pinfunction "A_A") (pintype "passive"))
    )
    (net (code "57") (name "Net-($$B29-P)") (class "Default")
      (node (ref "$$B29") (pin "A") (pinfunction "P_A") (pintype "passive"))
      (node (ref "$$D29") (pin "A") (pinfunction "A_A") (pintype "passive"))
    )
    (net (code "58") (name "Net-($$B30-P)") (class "Default")
      (node (ref "$$B30") (pin "A") (pinfunction "P_A") (pintype "passive"))
      (node (ref "$$D30") (pin "A") (pinfunction "A_A") (pintype "passive"))
    )
    (net (code "59") (name "Net-($$B31-P)") (class "Default")
      (node (ref "$$B31") (pin "A") (pinfunction "P_A") (pintype "passive"))
      (node (ref "$$D31") (pin "A") (pinfunction "A_A") (pintype "passive"))
    )
    (net (code "60") (name "Net-($$B32-P)") (class "Default")
      (node (ref "$$B32") (pin "A") (pinfunction "P_A") (pintype "passive"))
      (node (ref "$$D32") (pin "A") (pinfunction "A_A") (pintype "passive"))
    )
    (net (code "61") (name "Net-($$B33-P)") (class "Default")
      (node (ref "$$B33") (pin "A") (pinfunction "P_A") (pintype "passive"))
      (node (ref "$$D33") (pin "A") (pinfunction "A_A") (pintype "passive"))
    )
    (net (code "62") (name "Net-($$B34-P)") (class "Default")
      (node (ref "$$B34") (pin "A") (pinfunction "P_A") (pintype "passive"))
      (node (ref "$$D34") (pin "A") (pinfunction "A_A") (pintype "passive"))
    )
    (net (code "63") (name "Net-($$B35-P)") (class "Default")
      (node (ref "$$B35") (pin "A") (pinfunction "P_A") (pintype "passive"))
      (node (ref "$$D35") (pin "A") (pinfunction "A_A") (pintype "passive"))
    )
    (net (code "64") (name "Net-($$B36-P)") (class "Default")
      (node (ref "$$B36") (pin "A") (pinfunction "P_A") (pintype "passive"))
      (node (ref "$$D36") (pin "A") (pinfunction "A_A") (pintype "passive"))
    )
    (net (code "65") (name "Net-($$B37-P)") (class "Default")
      (node (ref "$$B37") (pin "A") (pinfunction "P_A") (pintype "passive"))
      (node (ref "$$D37") (pin "A") (pinfunction "A_A") (pintype "passive"))
    )
    (net (code "66") (name "Net-($$B38-P)") (class "Default")
      (node (ref "$$B38") (pin "A") (pinfunction "P_A") (pintype "passive"))
      (node (ref "$$D38") (pin "A") (pinfunction "A_A") (pintype "passive"))
    )
    (net (code "67") (name "Net-($$B39-P)") (class "Default")
      (node (ref "$$B39") (pin "A") (pinfunction "P_A") (pintype "passive"))
      (node (ref "$$D39") (pin "A") (pinfunction "A_A") (pintype "passive"))
    )
    (net (code "68") (name "Net-($$B40-P)") (class "Default")
      (node (ref "$$B40") (pin "A") (pinfunction "P_A") (pintype "passive"))
      (node (ref "$$D40") (pin "A") (pinfunction "A_A") (pintype "passive"))
    )
    (net (code "69") (name "Net-($$B41-P)") (class "Default")
      (node (ref "$$B41") (pin "A") (pinfunction "P_A") (pintype "passive"))
      (node (ref "$$D41") (pin "A") (pinfunction "A_A") (pintype "passive"))
    )
    (net (code "70") (name "Net-($$B42-P)") (class "Default")
      (node (ref "$$B42") (pin "A") (pinfunction "P_A") (pintype "passive"))
      (node (ref "$$D42") (pin "A") (pinfunction "A_A") (pintype "passive"))
    )
    (net (code "71") (name "Net-($$B43-P)") (class "Default")
      (node (ref "$$B43") (pin "A") (pinfunction "P_A") (pintype "passive"))
      (node (ref "$$D43") (pin "A") (pinfunction "A_A") (pintype "passive"))
    )
    (net (code "72") (name "Net-($$B44-P)") (class "Default")
      (node (ref "$$B44") (pin "A") (pinfunction "P_A") (pintype "passive"))
      (node (ref "$$D44") (pin "A") (pinfunction "A_A") (pintype "passive"))
    )
    (net (code "73") (name "Net-($$B45-P)") (class "Default")
      (node (ref "$$B45") (pin "A") (pinfunction "P_A") (pintype "passive"))
      (node (ref "$$D45") (pin "A") (pinfunction "A_A") (pintype "passive"))
    )
    (net (code "74") (name "Net-($$B46-P)") (class "Default")
      (node (ref "$$B46") (pin "A") (pinfunction "P_A") (pintype "passive"))
      (node (ref "$$D46") (pin "A") (pinfunction "A_A") (pintype "passive"))
    )
    (net (code "75") (name "Net-($$B48-P)") (class "Default")
      (node (ref "$$B48") (pin "A") (pinfunction "P_A") (pintype "passive"))
      (node (ref "$$D47") (pin "A") (pinfunction "A_A") (pintype "passive"))
    )
    (net (code "76") (name "Net-($$B49-P)") (class "Default")
      (node (ref "$$B49") (pin "A") (pinfunction "P_A") (pintype "passive"))
      (node (ref "$$D48") (pin "A") (pinfunction "A_A") (pintype "passive"))
    )
    (net (code "77") (name "Net-($$B50-P)") (class "Default")
      (node (ref "$$B50") (pin "A") (pinfunction "P_A") (pintype "passive"))
      (node (ref "$$D49") (pin "A") (pinfunction "A_A") (pintype "passive"))
    )
    (net (code "78") (name "Net-($$B51-P)") (class "Default")
      (node (ref "$$B51") (pin "A") (pinfunction "P_A") (pintype "passive"))
      (node (ref "$$D50") (pin "A") (pinfunction "A_A") (pintype "passive"))
    )
    (net (code "79") (name "Net-($$B52-P)") (class "Default")
      (node (ref "$$B52") (pin "A") (pinfunction "P_A") (pintype "passive"))
      (node (ref "$$D51") (pin "A") (pinfunction "A_A") (pintype "passive"))
    )
    (net (code "80") (name "Net-($$B53-P)") (class "Default")
      (node (ref "$$B53") (pin "A") (pinfunction "P_A") (pintype "passive"))
      (node (ref "$$D100") (pin "A") (pinfunction "A_A") (pintype "passive"))
    )
    (net (code "81") (name "Net-($$B54-P)") (class "Default")
      (node (ref "$$B54") (pin "A") (pinfunction "P_A") (pintype "passive"))
      (node (ref "$$D52") (pin "A") (pinfunction "A_A") (pintype "passive"))
    )
    (net (code "82") (name "Net-($$B55-P)") (class "Default")
      (node (ref "$$B55") (pin "A") (pinfunction "P_A") (pintype "passive"))
      (node (ref "$$D53") (pin "A") (pinfunction "A_A") (pintype "passive"))
    )
    (net (code "83") (name "Net-($$B56-P)") (class "Default")
      (node (ref "$$B56") (pin "A") (pinfunction "P_A") (pintype "passive"))
      (node (ref "$$D54") (pin "A") (pinfunction "A_A") (pintype "passive"))
    )
    (net (code "84") (name "Net-($$B57-P)") (class "Default")
      (node (ref "$$B57") (pin "A") (pinfunction "P_A") (pintype "passive"))
      (node (ref "$$D55") (pin "A") (pinfunction "A_A") (pintype "passive"))
    )
    (net (code "85") (name "Net-($$B58-P)") (class "Default")
      (node (ref "$$B58") (pin "A") (pinfunction "P_A") (pintype "passive"))
      (node (ref "$$D56") (pin "A") (pinfunction "A_A") (pintype "passive"))
    )
    (net (code "86") (name "Net-($$B59-P)") (class "Default")
      (node (ref "$$B59") (pin "A") (pinfunction "P_A") (pintype "passive"))
      (node (ref "$$D57") (pin "A") (pinfunction "A_A") (pintype "passive"))
    )
    (net (code "87") (name "Net-($$B60-P)") (class "Default")
      (node (ref "$$B60") (pin "A") (pinfunction "P_A") (pintype "passive"))
      (node (ref "$$D58") (pin "A") (pinfunction "A_A") (pintype "passive"))
    )
    (net (code "88") (name "Net-($$IC100-{slash}RESET)") (class "Default")
      (node (ref "$$IC100") (pin "2") (pinfunction "/RESET_2") (pintype "output"))
      (node (ref "$$R107") (pin "1") (pinfunction "1_1") (pintype "passive"))
      (node (ref "TFT1") (pin "10") (pinfunction "/RESET_10") (pintype "bidirectional"))
    )
    (net (code "89") (name "Net-($$PCB100-28{slash}GPIO28)") (class "Default")
      (node (ref "$$PCB100") (pin "28") (pinfunction "28/GPIO28_28") (pintype "bidirectional"))
      (node (ref "$$R116") (pin "2") (pinfunction "2_2") (pintype "passive"))
    )
    (net (code "90") (name "Net-($$PCB100-30{slash}GPIO29)") (class "Default")
      (node (ref "$$PCB100") (pin "30") (pinfunction "30/GPIO29_30") (pintype "bidirectional"))
      (node (ref "$$R115") (pin "2") (pinfunction "2_2") (pintype "passive"))
    )
    (net (code "91") (name "Net-($$PCB100-82{slash}GPIO44)") (class "Default")
      (node (ref "$$PCB100") (pin "82") (pinfunction "82/GPIO44_82") (pintype "bidirectional"))
      (node (ref "$$R108") (pin "2") (pinfunction "2_2") (pintype "passive"))
    )
    (net (code "92") (name "Net-($$PCB100-84{slash}GPIO45)") (class "Default")
      (node (ref "$$PCB100") (pin "84") (pinfunction "84/GPIO45_84") (pintype "bidirectional"))
      (node (ref "$$R117") (pin "2") (pinfunction "2_2") (pintype "passive"))
    )
    (net (code "93") (name "Net-($$PCB100-168{slash}USB_OTGID)") (class "Default")
      (node (ref "$$PCB100") (pin "168") (pinfunction "168/USB_OTGID_168") (pintype "bidirectional"))
      (node (ref "$$R109") (pin "2") (pinfunction "2_2") (pintype "passive"))
    )
    (net (code "94") (name "Net-($$Q100-B)") (class "Default")
      (node (ref "$$Q100") (pin "1") (pinfunction "B_1") (pintype "passive"))
      (node (ref "$$R102") (pin "2") (pinfunction "2_2") (pintype "passive"))
    )
    (net (code "95") (name "Net-($$Q100-C)") (class "Default")
      (node (ref "$$Q100") (pin "3") (pinfunction "C_3") (pintype "passive"))
      (node (ref "TFT1") (pin "1") (pinfunction "LEDK_1") (pintype "bidirectional"))
    )
    (net (code "96") (name "Net-($$R100-Pad1)") (class "Default")
      (node (ref "$$R100") (pin "1") (pinfunction "1_1") (pintype "passive"))
      (node (ref "TFT1") (pin "2") (pinfunction "LEDA_2") (pintype "bidirectional"))
    )
    (net (code "97") (name "Net-($$R101-Pad1)") (class "Default")
      (node (ref "$$R101") (pin "1") (pinfunction "1_1") (pintype "passive"))
      (node (ref "TFT1") (pin "3") (pinfunction "LEDA_3") (pintype "bidirectional"))
    )
    (net (code "98") (name "Net-($$R104-Pad1)") (class "Default")
      (node (ref "$$R104") (pin "1") (pinfunction "1_1") (pintype "passive"))
      (node (ref "TFT1") (pin "5") (pinfunction "LEDA_5") (pintype "bidirectional"))
    )
    (net (code "99") (name "Net-($$R106-Pad1)") (class "Default")
      (node (ref "$$R106") (pin "1") (pinfunction "1_1") (pintype "passive"))
      (node (ref "TFT1") (pin "4") (pinfunction "LEDA_4") (pintype "bidirectional"))
    )
    (net (code "100") (name "Net-($$R114-Pad1)") (class "Default")
      (node (ref "$$R114") (pin "1") (pinfunction "1_1") (pintype "passive"))
      (node (ref "LED1") (pin "A") (pinfunction "A_A") (pintype "passive"))
    )
    (net (code "101") (name "Net-($$U$100-EN2)") (class "Default")
      (node (ref "$$C118") (pin "1") (pinfunction "1_1") (pintype "passive"))
      (node (ref "$$R113") (pin "1") (pinfunction "1_1") (pintype "passive"))
      (node (ref "$$U$100") (pin "12") (pinfunction "EN2_12") (pintype "bidirectional"))
    )
    (net (code "102") (name "Net-($$U$100-FB1)") (class "Default")
      (node (ref "$$C119") (pin "2") (pinfunction "2_2") (pintype "passive"))
      (node (ref "$$SJ100") (pin "1") (pinfunction "1_1") (pintype "passive"))
      (node (ref "$$SJ102") (pin "2") (pinfunction "2_2") (pintype "passive"))
      (node (ref "$$U$100") (pin "2") (pinfunction "FB1_2") (pintype "bidirectional"))
    )
    (net (code "103") (name "Net-($$U$100-FB2)") (class "Default")
      (node (ref "$$C117") (pin "2") (pinfunction "2_2") (pintype "passive"))
      (node (ref "$$SJ101") (pin "2") (pinfunction "2_2") (pintype "passive"))
      (node (ref "$$SJ103") (pin "1") (pinfunction "1_1") (pintype "passive"))
      (node (ref "$$U$100") (pin "10") (pinfunction "FB2_10") (pintype "bidirectional"))
    )
    (net (code "104") (name "Net-($$U$100-LX1)") (class "Default")
      (node (ref "$$L101") (pin "1") (pinfunction "1_1") (pintype "passive"))
      (node (ref "$$U$100") (pin "8") (pinfunction "LX1_8") (pintype "bidirectional"))
    )
    (net (code "105") (name "Net-($$U$100-LX2)") (class "Default")
      (node (ref "$$L100") (pin "1") (pinfunction "1_1") (pintype "passive"))
      (node (ref "$$U$100") (pin "4") (pinfunction "LX2_4") (pintype "bidirectional"))
    )
    (net (code "106") (name "Net-(TFT1-DB0)") (class "Default")
      (node (ref "TFT1") (pin "15") (pinfunction "DB17_15") (pintype "bidirectional"))
      (node (ref "TFT1") (pin "16") (pinfunction "DB16_16") (pintype "bidirectional"))
      (node (ref "TFT1") (pin "17") (pinfunction "DB15_17") (pintype "bidirectional"))
      (node (ref "TFT1") (pin "18") (pinfunction "DB14_18") (pintype "bidirectional"))
      (node (ref "TFT1") (pin "19") (pinfunction "DB13_19") (pintype "bidirectional"))
      (node (ref "TFT1") (pin "20") (pinfunction "DB12_20") (pintype "bidirectional"))
      (node (ref "TFT1") (pin "21") (pinfunction "DB11_21") (pintype "bidirectional"))
      (node (ref "TFT1") (pin "22") (pinfunction "DB10_22") (pintype "bidirectional"))
      (node (ref "TFT1") (pin "23") (pinfunction "DB9_23") (pintype "bidirectional"))
      (node (ref "TFT1") (pin "24") (pinfunction "DB8_24") (pintype "bidirectional"))
      (node (ref "TFT1") (pin "25") (pinfunction "DB7_25") (pintype "bidirectional"))
      (node (ref "TFT1") (pin "26") (pinfunction "DB6_26") (pintype "bidirectional"))
      (node (ref "TFT1") (pin "27") (pinfunction "DB5_27") (pintype "bidirectional"))
      (node (ref "TFT1") (pin "28") (pinfunction "DB4_28") (pintype "bidirectional"))
      (node (ref "TFT1") (pin "29") (pinfunction "DB3_29") (pintype "bidirectional"))
      (node (ref "TFT1") (pin "30") (pinfunction "DB2_30") (pintype "bidirectional"))
      (node (ref "TFT1") (pin "31") (pinfunction "DB1_31") (pintype "bidirectional"))
      (node (ref "TFT1") (pin "32") (pinfunction "DB0_32") (pintype "bidirectional"))
    )
    (net (code "107") (name "Net-(U$4-BYP)") (class "Default")
      (node (ref "$$C121") (pin "1") (pinfunction "1_1") (pintype "passive"))
      (node (ref "U$4") (pin "4") (pinfunction "BYP_4") (pintype "bidirectional"))
    )
    (net (code "108") (name "Net-(UTSC-IN2{slash}GPIO-2)") (class "Default")
      (node (ref "$$R102") (pin "1") (pinfunction "1_1") (pintype "passive"))
      (node (ref "$$R103") (pin "2") (pinfunction "2_2") (pintype "passive"))
      (node (ref "UTSC") (pin "11") (pinfunction "IN2/GPIO-2_11") (pintype "bidirectional"))
    )
    (net (code "109") (name "ROW_0") (class "Default")
      (node (ref "$$D53") (pin "C") (pinfunction "C_C") (pintype "passive"))
      (node (ref "$$D54") (pin "C") (pinfunction "C_C") (pintype "passive"))
      (node (ref "$$D55") (pin "C") (pinfunction "C_C") (pintype "passive"))
      (node (ref "$$D56") (pin "C") (pinfunction "C_C") (pintype "passive"))
      (node (ref "$$D57") (pin "C") (pinfunction "C_C") (pintype "passive"))
      (node (ref "$$D58") (pin "C") (pinfunction "C_C") (pintype "passive"))
      (node (ref "$$PCB100") (pin "3") (pinfunction "3/GPIO0_3") (pintype "bidirectional"))
    )
    (net (code "110") (name "ROW_1") (class "Default")
      (node (ref "$$D100") (pin "C") (pinfunction "C_C") (pintype "passive"))
      (node (ref "$$D48") (pin "C") (pinfunction "C_C") (pintype "passive"))
      (node (ref "$$D49") (pin "C") (pinfunction "C_C") (pintype "passive"))
      (node (ref "$$D50") (pin "C") (pinfunction "C_C") (pintype "passive"))
      (node (ref "$$D51") (pin "C") (pinfunction "C_C") (pintype "passive"))
      (node (ref "$$D52") (pin "C") (pinfunction "C_C") (pintype "passive"))
      (node (ref "$$PCB100") (pin "60") (pinfunction "60/GPIO37_60") (pintype "bidirectional"))
    )
    (net (code "111") (name "ROW_2") (class "Default")
      (node (ref "$$D43") (pin "C") (pinfunction "C_C") (pintype "passive"))
      (node (ref "$$D44") (pin "C") (pinfunction "C_C") (pintype "passive"))
      (node (ref "$$D45") (pin "C") (pinfunction "C_C") (pintype "passive"))
      (node (ref "$$D46") (pin "C") (pinfunction "C_C") (pintype "passive"))
      (node (ref "$$D47") (pin "C") (pinfunction "C_C") (pintype "passive"))
      (node (ref "$$PCB100") (pin "58") (pinfunction "58/GPIO36_58") (pintype "bidirectional"))
    )
    (net (code "112") (name "ROW_3") (class "Default")
      (node (ref "$$D37") (pin "C") (pinfunction "C_C") (pintype "passive"))
      (node (ref "$$D38") (pin "C") (pinfunction "C_C") (pintype "passive"))
      (node (ref "$$D39") (pin "C") (pinfunction "C_C") (pintype "passive"))
      (node (ref "$$D40") (pin "C") (pinfunction "C_C") (pintype "passive"))
      (node (ref "$$D41") (pin "C") (pinfunction "C_C") (pintype "passive"))
      (node (ref "$$D42") (pin "C") (pinfunction "C_C") (pintype "passive"))
      (node (ref "$$PCB100") (pin "54") (pinfunction "54/GPIO35_54") (pintype "bidirectional"))
    )
    (net (code "113") (name "ROW_4") (class "Default")
      (node (ref "$$D31") (pin "C") (pinfunction "C_C") (pintype "passive"))
      (node (ref "$$D32") (pin "C") (pinfunction "C_C") (pintype "passive"))
      (node (ref "$$D33") (pin "C") (pinfunction "C_C") (pintype "passive"))
      (node (ref "$$D34") (pin "C") (pinfunction "C_C") (pintype "passive"))
      (node (ref "$$D35") (pin "C") (pinfunction "C_C") (pintype "passive"))
      (node (ref "$$D36") (pin "C") (pinfunction "C_C") (pintype "passive"))
      (node (ref "$$PCB100") (pin "52") (pinfunction "52/GPIO34_52") (pintype "bidirectional"))
    )
    (net (code "114") (name "ROW_5") (class "Default")
      (node (ref "$$D25") (pin "C") (pinfunction "C_C") (pintype "passive"))
      (node (ref "$$D26") (pin "C") (pinfunction "C_C") (pintype "passive"))
      (node (ref "$$D27") (pin "C") (pinfunction "C_C") (pintype "passive"))
      (node (ref "$$D28") (pin "C") (pinfunction "C_C") (pintype "passive"))
      (node (ref "$$D29") (pin "C") (pinfunction "C_C") (pintype "passive"))
      (node (ref "$$D30") (pin "C") (pinfunction "C_C") (pintype "passive"))
      (node (ref "$$PCB100") (pin "48") (pinfunction "48/GPIO33_48") (pintype "bidirectional"))
    )
    (net (code "115") (name "ROW_6") (class "Default")
      (node (ref "$$D19") (pin "C") (pinfunction "C_C") (pintype "passive"))
      (node (ref "$$D20") (pin "C") (pinfunction "C_C") (pintype "passive"))
      (node (ref "$$D21") (pin "C") (pinfunction "C_C") (pintype "passive"))
      (node (ref "$$D22") (pin "C") (pinfunction "C_C") (pintype "passive"))
      (node (ref "$$D23") (pin "C") (pinfunction "C_C") (pintype "passive"))
      (node (ref "$$D24") (pin "C") (pinfunction "C_C") (pintype "passive"))
      (node (ref "$$PCB100") (pin "46") (pinfunction "46/GPIO32_46") (pintype "bidirectional"))
    )
    (net (code "116") (name "ROW_7") (class "Default")
      (node (ref "$$D13") (pin "C") (pinfunction "C_C") (pintype "passive"))
      (node (ref "$$D14") (pin "C") (pinfunction "C_C") (pintype "passive"))
      (node (ref "$$D15") (pin "C") (pinfunction "C_C") (pintype "passive"))
      (node (ref "$$D16") (pin "C") (pinfunction "C_C") (pintype "passive"))
      (node (ref "$$D17") (pin "C") (pinfunction "C_C") (pintype "passive"))
      (node (ref "$$D18") (pin "C") (pinfunction "C_C") (pintype "passive"))
      (node (ref "$$PCB100") (pin "36") (pinfunction "36/GPIO31_36") (pintype "bidirectional"))
    )
    (net (code "117") (name "ROW_8") (class "Default")
      (node (ref "$$D10") (pin "C") (pinfunction "C_C") (pintype "passive"))
      (node (ref "$$D11") (pin "C") (pinfunction "C_C") (pintype "passive"))
      (node (ref "$$D12") (pin "C") (pinfunction "C_C") (pintype "passive"))
      (node (ref "$$D7") (pin "C") (pinfunction "C_C") (pintype "passive"))
      (node (ref "$$D8") (pin "C") (pinfunction "C_C") (pintype "passive"))
      (node (ref "$$D9") (pin "C") (pinfunction "C_C") (pintype "passive"))
      (node (ref "$$PCB100") (pin "64") (pinfunction "64/GPIO38_64") (pintype "bidirectional"))
    )
    (net (code "118") (name "ROW_9") (class "Default")
      (node (ref "$$D1") (pin "C") (pinfunction "C_C") (pintype "passive"))
      (node (ref "$$D2") (pin "C") (pinfunction "C_C") (pintype "passive"))
      (node (ref "$$D3") (pin "C") (pinfunction "C_C") (pintype "passive"))
      (node (ref "$$D4") (pin "C") (pinfunction "C_C") (pintype "passive"))
      (node (ref "$$D5") (pin "C") (pinfunction "C_C") (pintype "passive"))
      (node (ref "$$D6") (pin "C") (pinfunction "C_C") (pintype "passive"))
      (node (ref "$$PCB100") (pin "5") (pinfunction "5/GPIO1_5") (pintype "bidirectional"))
    )
    (net (code "119") (name "RT_CS_3V") (class "Default")
      (node (ref "$$PCB100") (pin "23") (pinfunction "23/GPIO7_23") (pintype "bidirectional"))
      (node (ref "$$R105") (pin "2") (pinfunction "2_2") (pintype "passive"))
      (node (ref "UTSC") (pin "5") (pinfunction "SDAT_5") (pintype "bidirectional"))
    )
    (net (code "120") (name "RT_INT") (class "Default")
      (node (ref "$$PCB100") (pin "81") (pinfunction "81/GPIO24_81") (pintype "bidirectional"))
      (node (ref "$$R112") (pin "1") (pinfunction "1_1") (pintype "passive"))
      (node (ref "UTSC") (pin "2") (pinfunction "INTERRUPT_2") (pintype "bidirectional"))
    )
    (net (code "121") (name "SCLK") (class "Default")
      (node (ref "$$PCB100") (pin "35") (pinfunction "35/GPIO11_35") (pintype "bidirectional"))
      (node (ref "$$R110") (pin "2") (pinfunction "2_2") (pintype "passive"))
      (node (ref "TFT1") (pin "37") (pinfunction "RS_SCL_37") (pintype "bidirectional"))
      (node (ref "UTSC") (pin "4") (pinfunction "SCLK_4") (pintype "bidirectional"))
    )
    (net (code "122") (name "TFT_3V3") (class "Default")
      (node (ref "$$IC100") (pin "3") (pinfunction "VCC_3") (pintype "power_in"))
      (node (ref "$$R100") (pin "2") (pinfunction "2_2") (pintype "passive"))
      (node (ref "$$R101") (pin "2") (pinfunction "2_2") (pintype "passive"))
      (node (ref "$$R103") (pin "1") (pinfunction "1_1") (pintype "passive"))
      (node (ref "$$R104") (pin "2") (pinfunction "2_2") (pintype "passive"))
      (node (ref "$$R105") (pin "1") (pinfunction "1_1") (pintype "passive"))
      (node (ref "$$R106") (pin "2") (pinfunction "2_2") (pintype "passive"))
      (node (ref "$$R107") (pin "2") (pinfunction "2_2") (pintype "passive"))
      (node (ref "$$R110") (pin "1") (pinfunction "1_1") (pintype "passive"))
      (node (ref "$$R111") (pin "1") (pinfunction "1_1") (pintype "passive"))
      (node (ref "$$U$101") (pin "5") (pinfunction "OUT_5") (pintype "bidirectional"))
      (node (ref "TFT1") (pin "40") (pinfunction "IOVCC_40") (pintype "bidirectional"))
      (node (ref "TFT1") (pin "41") (pinfunction "IOVCC_41") (pintype "bidirectional"))
      (node (ref "TFT1") (pin "42") (pinfunction "VCI_42") (pintype "bidirectional"))
      (node (ref "TFT1") (pin "7") (pinfunction "IM1_7") (pintype "bidirectional"))
      (node (ref "TFT1") (pin "8") (pinfunction "IM2_8") (pintype "bidirectional"))
      (node (ref "TFT1") (pin "9") (pinfunction "IM3_9") (pintype "bidirectional"))
      (node (ref "UTSC") (pin "14") (pinfunction "VIO_14") (pintype "bidirectional"))
      (node (ref "UTSC") (pin "6") (pinfunction "VCC_6") (pintype "bidirectional"))
      (node (ref "UTSC") (pin "9") (pinfunction "IN1/GPIO-1/MODE_9") (pintype "bidirectional"))
    )
    (net (code "123") (name "TFT_CS_3V") (class "Default")
      (node (ref "$$PCB100") (pin "27") (pinfunction "27/GPIO8_27") (pintype "bidirectional"))
      (node (ref "TFT1") (pin "38") (pinfunction "/CS_38") (pintype "bidirectional"))
    )
    (net (code "124") (name "TFT_DC_3V") (class "Default")
      (node (ref "$$PCB100") (pin "83") (pinfunction "83/GPIO25_83") (pintype "bidirectional"))
      (node (ref "TFT1") (pin "36") (pinfunction "/WR_RS_36") (pintype "bidirectional"))
    )
    (net (code "125") (name "USB_DM") (class "Default")
      (node (ref "$$J100") (pin "2") (pinfunction "2_2") (pintype "passive"))
      (node (ref "$$PCB100") (pin "165") (pinfunction "165/USB_DP**_165") (pintype "bidirectional"))
    )
    (net (code "126") (name "USB_DP") (class "Default")
      (node (ref "$$J100") (pin "3") (pinfunction "3_3") (pintype "passive"))
      (node (ref "$$PCB100") (pin "167") (pinfunction "167/USB_DM**_167") (pintype "bidirectional"))
    )
    (net (code "127") (name "VBUSA") (class "Default")
      (node (ref "$$C110") (pin "1") (pinfunction "1_1") (pintype "passive"))
      (node (ref "$$C111") (pin "1") (pinfunction "1_1") (pintype "passive"))
      (node (ref "$$J100") (pin "1") (pinfunction "1_1") (pintype "passive"))
      (node (ref "$$SJ1") (pin "1") (pinfunction "1_1") (pintype "passive"))
    )
    (net (code "128") (name "X+") (class "Default")
      (node (ref "TFT1") (pin "45") (pinfunction "TP_SDA_45") (pintype "bidirectional"))
      (node (ref "UTSC") (pin "13") (pinfunction "X+_13") (pintype "bidirectional"))
    )
    (net (code "129") (name "X-") (class "Default")
      (node (ref "TFT1") (pin "44") (pinfunction "TP_SCK_44") (pintype "bidirectional"))
      (node (ref "UTSC") (pin "16") (pinfunction "X-_16") (pintype "bidirectional"))
    )
    (net (code "130") (name "Y+") (class "Default")
      (node (ref "TFT1") (pin "46") (pinfunction "TP_IRQ_46") (pintype "bidirectional"))
      (node (ref "UTSC") (pin "15") (pinfunction "Y+_15") (pintype "bidirectional"))
    )
    (net (code "131") (name "Y-") (class "Default")
      (node (ref "TFT1") (pin "47") (pinfunction "TP_RES_47") (pintype "bidirectional"))
      (node (ref "UTSC") (pin "1") (pinfunction "Y-_1") (pintype "bidirectional"))
    )
    (net (code "132") (name "unconnected-($$B1-P1-PadA')") (class "Default")
      (node (ref "$$B1") (pin "A'") (pinfunction "P1_A'") (pintype "passive"))
    )
    (net (code "133") (name "unconnected-($$B1-S1-PadB')") (class "Default")
      (node (ref "$$B1") (pin "B'") (pinfunction "S1_B'") (pintype "passive"))
    )
    (net (code "134") (name "unconnected-($$B2-P1-PadA')") (class "Default")
      (node (ref "$$B2") (pin "A'") (pinfunction "P1_A'") (pintype "passive"))
    )
    (net (code "135") (name "unconnected-($$B2-S1-PadB')") (class "Default")
      (node (ref "$$B2") (pin "B'") (pinfunction "S1_B'") (pintype "passive"))
    )
    (net (code "136") (name "unconnected-($$B3-P1-PadA')") (class "Default")
      (node (ref "$$B3") (pin "A'") (pinfunction "P1_A'") (pintype "passive"))
    )
    (net (code "137") (name "unconnected-($$B3-S1-PadB')") (class "Default")
      (node (ref "$$B3") (pin "B'") (pinfunction "S1_B'") (pintype "passive"))
    )
    (net (code "138") (name "unconnected-($$B4-P1-PadA')") (class "Default")
      (node (ref "$$B4") (pin "A'") (pinfunction "P1_A'") (pintype "passive"))
    )
    (net (code "139") (name "unconnected-($$B4-S1-PadB')") (class "Default")
      (node (ref "$$B4") (pin "B'") (pinfunction "S1_B'") (pintype "passive"))
    )
    (net (code "140") (name "unconnected-($$B5-P1-PadA')") (class "Default")
      (node (ref "$$B5") (pin "A'") (pinfunction "P1_A'") (pintype "passive"))
    )
    (net (code "141") (name "unconnected-($$B5-S1-PadB')") (class "Default")
      (node (ref "$$B5") (pin "B'") (pinfunction "S1_B'") (pintype "passive"))
    )
    (net (code "142") (name "unconnected-($$B6-P1-PadA')") (class "Default")
      (node (ref "$$B6") (pin "A'") (pinfunction "P1_A'") (pintype "passive"))
    )
    (net (code "143") (name "unconnected-($$B6-S1-PadB')") (class "Default")
      (node (ref "$$B6") (pin "B'") (pinfunction "S1_B'") (pintype "passive"))
    )
    (net (code "144") (name "unconnected-($$B7-P1-PadA')") (class "Default")
      (node (ref "$$B7") (pin "A'") (pinfunction "P1_A'") (pintype "passive"))
    )
    (net (code "145") (name "unconnected-($$B7-S1-PadB')") (class "Default")
      (node (ref "$$B7") (pin "B'") (pinfunction "S1_B'") (pintype "passive"))
    )
    (net (code "146") (name "unconnected-($$B8-P1-PadA')") (class "Default")
      (node (ref "$$B8") (pin "A'") (pinfunction "P1_A'") (pintype "passive"))
    )
    (net (code "147") (name "unconnected-($$B8-S1-PadB')") (class "Default")
      (node (ref "$$B8") (pin "B'") (pinfunction "S1_B'") (pintype "passive"))
    )
    (net (code "148") (name "unconnected-($$B9-P1-PadA')") (class "Default")
      (node (ref "$$B9") (pin "A'") (pinfunction "P1_A'") (pintype "passive"))
    )
    (net (code "149") (name "unconnected-($$B9-S1-PadB')") (class "Default")
      (node (ref "$$B9") (pin "B'") (pinfunction "S1_B'") (pintype "passive"))
    )
    (net (code "150") (name "unconnected-($$B10-P1-PadA')") (class "Default")
      (node (ref "$$B10") (pin "A'") (pinfunction "P1_A'") (pintype "passive"))
    )
    (net (code "151") (name "unconnected-($$B10-S1-PadB')") (class "Default")
      (node (ref "$$B10") (pin "B'") (pinfunction "S1_B'") (pintype "passive"))
    )
    (net (code "152") (name "unconnected-($$B11-P1-PadA')") (class "Default")
      (node (ref "$$B11") (pin "A'") (pinfunction "P1_A'") (pintype "passive"))
    )
    (net (code "153") (name "unconnected-($$B11-S1-PadB')") (class "Default")
      (node (ref "$$B11") (pin "B'") (pinfunction "S1_B'") (pintype "passive"))
    )
    (net (code "154") (name "unconnected-($$B12-P1-PadA')") (class "Default")
      (node (ref "$$B12") (pin "A'") (pinfunction "P1_A'") (pintype "passive"))
    )
    (net (code "155") (name "unconnected-($$B12-S1-PadB')") (class "Default")
      (node (ref "$$B12") (pin "B'") (pinfunction "S1_B'") (pintype "passive"))
    )
    (net (code "156") (name "unconnected-($$B13-P1-PadA')") (class "Default")
      (node (ref "$$B13") (pin "A'") (pinfunction "P1_A'") (pintype "passive"))
    )
    (net (code "157") (name "unconnected-($$B13-S1-PadB')") (class "Default")
      (node (ref "$$B13") (pin "B'") (pinfunction "S1_B'") (pintype "passive"))
    )
    (net (code "158") (name "unconnected-($$B14-P1-PadA')") (class "Default")
      (node (ref "$$B14") (pin "A'") (pinfunction "P1_A'") (pintype "passive"))
    )
    (net (code "159") (name "unconnected-($$B14-S1-PadB')") (class "Default")
      (node (ref "$$B14") (pin "B'") (pinfunction "S1_B'") (pintype "passive"))
    )
    (net (code "160") (name "unconnected-($$B15-P1-PadA')") (class "Default")
      (node (ref "$$B15") (pin "A'") (pinfunction "P1_A'") (pintype "passive"))
    )
    (net (code "161") (name "unconnected-($$B15-S1-PadB')") (class "Default")
      (node (ref "$$B15") (pin "B'") (pinfunction "S1_B'") (pintype "passive"))
    )
    (net (code "162") (name "unconnected-($$B16-P1-PadA')") (class "Default")
      (node (ref "$$B16") (pin "A'") (pinfunction "P1_A'") (pintype "passive"))
    )
    (net (code "163") (name "unconnected-($$B16-S1-PadB')") (class "Default")
      (node (ref "$$B16") (pin "B'") (pinfunction "S1_B'") (pintype "passive"))
    )
    (net (code "164") (name "unconnected-($$B17-P1-PadA')") (class "Default")
      (node (ref "$$B17") (pin "A'") (pinfunction "P1_A'") (pintype "passive"))
    )
    (net (code "165") (name "unconnected-($$B17-S1-PadB')") (class "Default")
      (node (ref "$$B17") (pin "B'") (pinfunction "S1_B'") (pintype "passive"))
    )
    (net (code "166") (name "unconnected-($$B18-P1-PadA')") (class "Default")
      (node (ref "$$B18") (pin "A'") (pinfunction "P1_A'") (pintype "passive"))
    )
    (net (code "167") (name "unconnected-($$B18-S1-PadB')") (class "Default")
      (node (ref "$$B18") (pin "B'") (pinfunction "S1_B'") (pintype "passive"))
    )
    (net (code "168") (name "unconnected-($$B19-P1-PadA')") (class "Default")
      (node (ref "$$B19") (pin "A'") (pinfunction "P1_A'") (pintype "passive"))
    )
    (net (code "169") (name "unconnected-($$B19-S1-PadB')") (class "Default")
      (node (ref "$$B19") (pin "B'") (pinfunction "S1_B'") (pintype "passive"))
    )
    (net (code "170") (name "unconnected-($$B20-P1-PadA')") (class "Default")
      (node (ref "$$B20") (pin "A'") (pinfunction "P1_A'") (pintype "passive"))
    )
    (net (code "171") (name "unconnected-($$B20-S1-PadB')") (class "Default")
      (node (ref "$$B20") (pin "B'") (pinfunction "S1_B'") (pintype "passive"))
    )
    (net (code "172") (name "unconnected-($$B21-P1-PadA')") (class "Default")
      (node (ref "$$B21") (pin "A'") (pinfunction "P1_A'") (pintype "passive"))
    )
    (net (code "173") (name "unconnected-($$B21-S1-PadB')") (class "Default")
      (node (ref "$$B21") (pin "B'") (pinfunction "S1_B'") (pintype "passive"))
    )
    (net (code "174") (name "unconnected-($$B22-P1-PadA')") (class "Default")
      (node (ref "$$B22") (pin "A'") (pinfunction "P1_A'") (pintype "passive"))
    )
    (net (code "175") (name "unconnected-($$B22-S1-PadB')") (class "Default")
      (node (ref "$$B22") (pin "B'") (pinfunction "S1_B'") (pintype "passive"))
    )
    (net (code "176") (name "unconnected-($$B23-P1-PadA')") (class "Default")
      (node (ref "$$B23") (pin "A'") (pinfunction "P1_A'") (pintype "passive"))
    )
    (net (code "177") (name "unconnected-($$B23-S1-PadB')") (class "Default")
      (node (ref "$$B23") (pin "B'") (pinfunction "S1_B'") (pintype "passive"))
    )
    (net (code "178") (name "unconnected-($$B24-P1-PadA')") (class "Default")
      (node (ref "$$B24") (pin "A'") (pinfunction "P1_A'") (pintype "passive"))
    )
    (net (code "179") (name "unconnected-($$B24-S1-PadB')") (class "Default")
      (node (ref "$$B24") (pin "B'") (pinfunction "S1_B'") (pintype "passive"))
    )
    (net (code "180") (name "unconnected-($$B25-P1-PadA')") (class "Default")
      (node (ref "$$B25") (pin "A'") (pinfunction "P1_A'") (pintype "passive"))
    )
    (net (code "181") (name "unconnected-($$B25-S1-PadB')") (class "Default")
      (node (ref "$$B25") (pin "B'") (pinfunction "S1_B'") (pintype "passive"))
    )
    (net (code "182") (name "unconnected-($$B26-P1-PadA')") (class "Default")
      (node (ref "$$B26") (pin "A'") (pinfunction "P1_A'") (pintype "passive"))
    )
    (net (code "183") (name "unconnected-($$B26-S1-PadB')") (class "Default")
      (node (ref "$$B26") (pin "B'") (pinfunction "S1_B'") (pintype "passive"))
    )
    (net (code "184") (name "unconnected-($$B27-P1-PadA')") (class "Default")
      (node (ref "$$B27") (pin "A'") (pinfunction "P1_A'") (pintype "passive"))
    )
    (net (code "185") (name "unconnected-($$B27-S1-PadB')") (class "Default")
      (node (ref "$$B27") (pin "B'") (pinfunction "S1_B'") (pintype "passive"))
    )
    (net (code "186") (name "unconnected-($$B28-P1-PadA')") (class "Default")
      (node (ref "$$B28") (pin "A'") (pinfunction "P1_A'") (pintype "passive"))
    )
    (net (code "187") (name "unconnected-($$B28-S1-PadB')") (class "Default")
      (node (ref "$$B28") (pin "B'") (pinfunction "S1_B'") (pintype "passive"))
    )
    (net (code "188") (name "unconnected-($$B29-P1-PadA')") (class "Default")
      (node (ref "$$B29") (pin "A'") (pinfunction "P1_A'") (pintype "passive"))
    )
    (net (code "189") (name "unconnected-($$B29-S1-PadB')") (class "Default")
      (node (ref "$$B29") (pin "B'") (pinfunction "S1_B'") (pintype "passive"))
    )
    (net (code "190") (name "unconnected-($$B30-P1-PadA')") (class "Default")
      (node (ref "$$B30") (pin "A'") (pinfunction "P1_A'") (pintype "passive"))
    )
    (net (code "191") (name "unconnected-($$B30-S1-PadB')") (class "Default")
      (node (ref "$$B30") (pin "B'") (pinfunction "S1_B'") (pintype "passive"))
    )
    (net (code "192") (name "unconnected-($$B31-P1-PadA')") (class "Default")
      (node (ref "$$B31") (pin "A'") (pinfunction "P1_A'") (pintype "passive"))
    )
    (net (code "193") (name "unconnected-($$B31-S1-PadB')") (class "Default")
      (node (ref "$$B31") (pin "B'") (pinfunction "S1_B'") (pintype "passive"))
    )
    (net (code "194") (name "unconnected-($$B32-P1-PadA')") (class "Default")
      (node (ref "$$B32") (pin "A'") (pinfunction "P1_A'") (pintype "passive"))
    )
    (net (code "195") (name "unconnected-($$B32-S1-PadB')") (class "Default")
      (node (ref "$$B32") (pin "B'") (pinfunction "S1_B'") (pintype "passive"))
    )
    (net (code "196") (name "unconnected-($$B33-P1-PadA')") (class "Default")
      (node (ref "$$B33") (pin "A'") (pinfunction "P1_A'") (pintype "passive"))
    )
    (net (code "197") (name "unconnected-($$B33-S1-PadB')") (class "Default")
      (node (ref "$$B33") (pin "B'") (pinfunction "S1_B'") (pintype "passive"))
    )
    (net (code "198") (name "unconnected-($$B34-P1-PadA')") (class "Default")
      (node (ref "$$B34") (pin "A'") (pinfunction "P1_A'") (pintype "passive"))
    )
    (net (code "199") (name "unconnected-($$B34-S1-PadB')") (class "Default")
      (node (ref "$$B34") (pin "B'") (pinfunction "S1_B'") (pintype "passive"))
    )
    (net (code "200") (name "unconnected-($$B35-P1-PadA')") (class "Default")
      (node (ref "$$B35") (pin "A'") (pinfunction "P1_A'") (pintype "passive"))
    )
    (net (code "201") (name "unconnected-($$B35-S1-PadB')") (class "Default")
      (node (ref "$$B35") (pin "B'") (pinfunction "S1_B'") (pintype "passive"))
    )
    (net (code "202") (name "unconnected-($$B36-P1-PadA')") (class "Default")
      (node (ref "$$B36") (pin "A'") (pinfunction "P1_A'") (pintype "passive"))
    )
    (net (code "203") (name "unconnected-($$B36-S1-PadB')") (class "Default")
      (node (ref "$$B36") (pin "B'") (pinfunction "S1_B'") (pintype "passive"))
    )
    (net (code "204") (name "unconnected-($$B37-P1-PadA')") (class "Default")
      (node (ref "$$B37") (pin "A'") (pinfunction "P1_A'") (pintype "passive"))
    )
    (net (code "205") (name "unconnected-($$B37-S1-PadB')") (class "Default")
      (node (ref "$$B37") (pin "B'") (pinfunction "S1_B'") (pintype "passive"))
    )
    (net (code "206") (name "unconnected-($$B38-P1-PadA')") (class "Default")
      (node (ref "$$B38") (pin "A'") (pinfunction "P1_A'") (pintype "passive"))
    )
    (net (code "207") (name "unconnected-($$B38-S1-PadB')") (class "Default")
      (node (ref "$$B38") (pin "B'") (pinfunction "S1_B'") (pintype "passive"))
    )
    (net (code "208") (name "unconnected-($$B39-P1-PadA')") (class "Default")
      (node (ref "$$B39") (pin "A'") (pinfunction "P1_A'") (pintype "passive"))
    )
    (net (code "209") (name "unconnected-($$B39-S1-PadB')") (class "Default")
      (node (ref "$$B39") (pin "B'") (pinfunction "S1_B'") (pintype "passive"))
    )
    (net (code "210") (name "unconnected-($$B40-P1-PadA')") (class "Default")
      (node (ref "$$B40") (pin "A'") (pinfunction "P1_A'") (pintype "passive"))
    )
    (net (code "211") (name "unconnected-($$B40-S1-PadB')") (class "Default")
      (node (ref "$$B40") (pin "B'") (pinfunction "S1_B'") (pintype "passive"))
    )
    (net (code "212") (name "unconnected-($$B41-P1-PadA')") (class "Default")
      (node (ref "$$B41") (pin "A'") (pinfunction "P1_A'") (pintype "passive"))
    )
    (net (code "213") (name "unconnected-($$B41-S1-PadB')") (class "Default")
      (node (ref "$$B41") (pin "B'") (pinfunction "S1_B'") (pintype "passive"))
    )
    (net (code "214") (name "unconnected-($$B42-P1-PadA')") (class "Default")
      (node (ref "$$B42") (pin "A'") (pinfunction "P1_A'") (pintype "passive"))
    )
    (net (code "215") (name "unconnected-($$B42-S1-PadB')") (class "Default")
      (node (ref "$$B42") (pin "B'") (pinfunction "S1_B'") (pintype "passive"))
    )
    (net (code "216") (name "unconnected-($$B43-P1-PadA')") (class "Default")
      (node (ref "$$B43") (pin "A'") (pinfunction "P1_A'") (pintype "passive"))
    )
    (net (code "217") (name "unconnected-($$B43-S1-PadB')") (class "Default")
      (node (ref "$$B43") (pin "B'") (pinfunction "S1_B'") (pintype "passive"))
    )
    (net (code "218") (name "unconnected-($$B44-P1-PadA')") (class "Default")
      (node (ref "$$B44") (pin "A'") (pinfunction "P1_A'") (pintype "passive"))
    )
    (net (code "219") (name "unconnected-($$B44-S1-PadB')") (class "Default")
      (node (ref "$$B44") (pin "B'") (pinfunction "S1_B'") (pintype "passive"))
    )
    (net (code "220") (name "unconnected-($$B45-P1-PadA')") (class "Default")
      (node (ref "$$B45") (pin "A'") (pinfunction "P1_A'") (pintype "passive"))
    )
    (net (code "221") (name "unconnected-($$B45-S1-PadB')") (class "Default")
      (node (ref "$$B45") (pin "B'") (pinfunction "S1_B'") (pintype "passive"))
    )
    (net (code "222") (name "unconnected-($$B46-P1-PadA')") (class "Default")
      (node (ref "$$B46") (pin "A'") (pinfunction "P1_A'") (pintype "passive"))
    )
    (net (code "223") (name "unconnected-($$B46-S1-PadB')") (class "Default")
      (node (ref "$$B46") (pin "B'") (pinfunction "S1_B'") (pintype "passive"))
    )
    (net (code "224") (name "unconnected-($$B48-P1-PadA')") (class "Default")
      (node (ref "$$B48") (pin "A'") (pinfunction "P1_A'") (pintype "passive"))
    )
    (net (code "225") (name "unconnected-($$B48-S1-PadB')") (class "Default")
      (node (ref "$$B48") (pin "B'") (pinfunction "S1_B'") (pintype "passive"))
    )
    (net (code "226") (name "unconnected-($$B49-P1-PadA')") (class "Default")
      (node (ref "$$B49") (pin "A'") (pinfunction "P1_A'") (pintype "passive"))
    )
    (net (code "227") (name "unconnected-($$B49-S1-PadB')") (class "Default")
      (node (ref "$$B49") (pin "B'") (pinfunction "S1_B'") (pintype "passive"))
    )
    (net (code "228") (name "unconnected-($$B50-P1-PadA')") (class "Default")
      (node (ref "$$B50") (pin "A'") (pinfunction "P1_A'") (pintype "passive"))
    )
    (net (code "229") (name "unconnected-($$B50-S1-PadB')") (class "Default")
      (node (ref "$$B50") (pin "B'") (pinfunction "S1_B'") (pintype "passive"))
    )
    (net (code "230") (name "unconnected-($$B51-P1-PadA')") (class "Default")
      (node (ref "$$B51") (pin "A'") (pinfunction "P1_A'") (pintype "passive"))
    )
    (net (code "231") (name "unconnected-($$B51-S1-PadB')") (class "Default")
      (node (ref "$$B51") (pin "B'") (pinfunction "S1_B'") (pintype "passive"))
    )
    (net (code "232") (name "unconnected-($$B52-P1-PadA')") (class "Default")
      (node (ref "$$B52") (pin "A'") (pinfunction "P1_A'") (pintype "passive"))
    )
    (net (code "233") (name "unconnected-($$B52-S1-PadB')") (class "Default")
      (node (ref "$$B52") (pin "B'") (pinfunction "S1_B'") (pintype "passive"))
    )
    (net (code "234") (name "unconnected-($$B53-P1-PadA')") (class "Default")
      (node (ref "$$B53") (pin "A'") (pinfunction "P1_A'") (pintype "passive"))
    )
    (net (code "235") (name "unconnected-($$B53-S1-PadB')") (class "Default")
      (node (ref "$$B53") (pin "B'") (pinfunction "S1_B'") (pintype "passive"))
    )
    (net (code "236") (name "unconnected-($$B54-P1-PadA')") (class "Default")
      (node (ref "$$B54") (pin "A'") (pinfunction "P1_A'") (pintype "passive"))
    )
    (net (code "237") (name "unconnected-($$B54-S1-PadB')") (class "Default")
      (node (ref "$$B54") (pin "B'") (pinfunction "S1_B'") (pintype "passive"))
    )
    (net (code "238") (name "unconnected-($$B55-P1-PadA')") (class "Default")
      (node (ref "$$B55") (pin "A'") (pinfunction "P1_A'") (pintype "passive"))
    )
    (net (code "239") (name "unconnected-($$B55-S1-PadB')") (class "Default")
      (node (ref "$$B55") (pin "B'") (pinfunction "S1_B'") (pintype "passive"))
    )
    (net (code "240") (name "unconnected-($$B56-P1-PadA')") (class "Default")
      (node (ref "$$B56") (pin "A'") (pinfunction "P1_A'") (pintype "passive"))
    )
    (net (code "241") (name "unconnected-($$B56-S1-PadB')") (class "Default")
      (node (ref "$$B56") (pin "B'") (pinfunction "S1_B'") (pintype "passive"))
    )
    (net (code "242") (name "unconnected-($$B57-P1-PadA')") (class "Default")
      (node (ref "$$B57") (pin "A'") (pinfunction "P1_A'") (pintype "passive"))
    )
    (net (code "243") (name "unconnected-($$B57-S1-PadB')") (class "Default")
      (node (ref "$$B57") (pin "B'") (pinfunction "S1_B'") (pintype "passive"))
    )
    (net (code "244") (name "unconnected-($$B58-P1-PadA')") (class "Default")
      (node (ref "$$B58") (pin "A'") (pinfunction "P1_A'") (pintype "passive"))
    )
    (net (code "245") (name "unconnected-($$B58-S1-PadB')") (class "Default")
      (node (ref "$$B58") (pin "B'") (pinfunction "S1_B'") (pintype "passive"))
    )
    (net (code "246") (name "unconnected-($$B59-P1-PadA')") (class "Default")
      (node (ref "$$B59") (pin "A'") (pinfunction "P1_A'") (pintype "passive"))
    )
    (net (code "247") (name "unconnected-($$B59-S1-PadB')") (class "Default")
      (node (ref "$$B59") (pin "B'") (pinfunction "S1_B'") (pintype "passive"))
    )
    (net (code "248") (name "unconnected-($$B60-P1-PadA')") (class "Default")
      (node (ref "$$B60") (pin "A'") (pinfunction "P1_A'") (pintype "passive"))
    )
    (net (code "249") (name "unconnected-($$B60-S1-PadB')") (class "Default")
      (node (ref "$$B60") (pin "B'") (pinfunction "S1_B'") (pintype "passive"))
    )
    (net (code "250") (name "unconnected-($$PCB100-1{slash}GND-Pad1)") (class "Default")
      (node (ref "$$PCB100") (pin "1") (pinfunction "1/GND_1") (pintype "bidirectional"))
    )
    (net (code "251") (name "unconnected-($$PCB100-4{slash}NC-Pad4)") (class "Default")
      (node (ref "$$PCB100") (pin "4") (pinfunction "4/NC_4") (pintype "bidirectional"))
    )
    (net (code "252") (name "unconnected-($$PCB100-6{slash}NC-Pad6)") (class "Default")
      (node (ref "$$PCB100") (pin "6") (pinfunction "6/NC_6") (pintype "bidirectional"))
    )
    (net (code "253") (name "unconnected-($$PCB100-7{slash}GND-Pad7)") (class "Default")
      (node (ref "$$PCB100") (pin "7") (pinfunction "7/GND_7") (pintype "bidirectional"))
    )
    (net (code "254") (name "unconnected-($$PCB100-8{slash}NC-Pad8)") (class "Default")
      (node (ref "$$PCB100") (pin "8") (pinfunction "8/NC_8") (pintype "bidirectional"))
    )
    (net (code "255") (name "unconnected-($$PCB100-9{slash}GPIO2-Pad9)") (class "Default")
      (node (ref "$$PCB100") (pin "9") (pinfunction "9/GPIO2_9") (pintype "bidirectional"))
    )
    (net (code "256") (name "unconnected-($$PCB100-10{slash}NC-Pad10)") (class "Default")
      (node (ref "$$PCB100") (pin "10") (pinfunction "10/NC_10") (pintype "bidirectional"))
    )
    (net (code "257") (name "unconnected-($$PCB100-11{slash}GPIO3-Pad11)") (class "Default")
      (node (ref "$$PCB100") (pin "11") (pinfunction "11/GPIO3_11") (pintype "bidirectional"))
    )
    (net (code "258") (name "unconnected-($$PCB100-12{slash}NC-Pad12)") (class "Default")
      (node (ref "$$PCB100") (pin "12") (pinfunction "12/NC_12") (pintype "bidirectional"))
    )
    (net (code "259") (name "unconnected-($$PCB100-13{slash}GND-Pad13)") (class "Default")
      (node (ref "$$PCB100") (pin "13") (pinfunction "13/GND_13") (pintype "bidirectional"))
    )
    (net (code "260") (name "unconnected-($$PCB100-14{slash}NC-Pad14)") (class "Default")
      (node (ref "$$PCB100") (pin "14") (pinfunction "14/NC_14") (pintype "bidirectional"))
    )
    (net (code "261") (name "unconnected-($$PCB100-15{slash}GPIO4-Pad15)") (class "Default")
      (node (ref "$$PCB100") (pin "15") (pinfunction "15/GPIO4_15") (pintype "bidirectional"))
    )
    (net (code "262") (name "unconnected-($$PCB100-16{slash}NC-Pad16)") (class "Default")
      (node (ref "$$PCB100") (pin "16") (pinfunction "16/NC_16") (pintype "bidirectional"))
    )
    (net (code "263") (name "unconnected-($$PCB100-17{slash}GPIO5-Pad17)") (class "Default")
      (node (ref "$$PCB100") (pin "17") (pinfunction "17/GPIO5_17") (pintype "bidirectional"))
    )
    (net (code "264") (name "unconnected-($$PCB100-18{slash}NC-Pad18)") (class "Default")
      (node (ref "$$PCB100") (pin "18") (pinfunction "18/NC_18") (pintype "bidirectional"))
    )
    (net (code "265") (name "unconnected-($$PCB100-19{slash}GND-Pad19)") (class "Default")
      (node (ref "$$PCB100") (pin "19") (pinfunction "19/GND_19") (pintype "bidirectional"))
    )
    (net (code "266") (name "unconnected-($$PCB100-20{slash}NC-Pad20)") (class "Default")
      (node (ref "$$PCB100") (pin "20") (pinfunction "20/NC_20") (pintype "bidirectional"))
    )
    (net (code "267") (name "unconnected-($$PCB100-21{slash}GPIO6-Pad21)") (class "Default")
      (node (ref "$$PCB100") (pin "21") (pinfunction "21/GPIO6_21") (pintype "bidirectional"))
    )
    (net (code "268") (name "unconnected-($$PCB100-22{slash}NC-Pad22)") (class "Default")
      (node (ref "$$PCB100") (pin "22") (pinfunction "22/NC_22") (pintype "bidirectional"))
    )
    (net (code "269") (name "unconnected-($$PCB100-24{slash}NC-Pad24)") (class "Default")
      (node (ref "$$PCB100") (pin "24") (pinfunction "24/NC_24") (pintype "bidirectional"))
    )
    (net (code "270") (name "unconnected-($$PCB100-25{slash}GND-Pad25)") (class "Default")
      (node (ref "$$PCB100") (pin "25") (pinfunction "25/GND_25") (pintype "bidirectional"))
    )
    (net (code "271") (name "unconnected-($$PCB100-26{slash}GND-Pad26)") (class "Default")
      (node (ref "$$PCB100") (pin "26") (pinfunction "26/GND_26") (pintype "bidirectional"))
    )
    (net (code "272") (name "unconnected-($$PCB100-31{slash}GND-Pad31)") (class "Default")
      (node (ref "$$PCB100") (pin "31") (pinfunction "31/GND_31") (pintype "bidirectional"))
    )
    (net (code "273") (name "unconnected-($$PCB100-32{slash}GND-Pad32)") (class "Default")
      (node (ref "$$PCB100") (pin "32") (pinfunction "32/GND_32") (pintype "bidirectional"))
    )
    (net (code "274") (name "unconnected-($$PCB100-34{slash}GPIO30-Pad34)") (class "Default")
      (node (ref "$$PCB100") (pin "34") (pinfunction "34/GPIO30_34") (pintype "bidirectional"))
    )
    (net (code "275") (name "unconnected-($$PCB100-37{slash}GND-Pad37)") (class "Default")
      (node (ref "$$PCB100") (pin "37") (pinfunction "37/GND_37") (pintype "bidirectional"))
    )
    (net (code "276") (name "unconnected-($$PCB100-38{slash}GND-Pad38)") (class "Default")
      (node (ref "$$PCB100") (pin "38") (pinfunction "38/GND_38") (pintype "bidirectional"))
    )
    (net (code "277") (name "unconnected-($$PCB100-39{slash}GPIO0-27_VREF-Pad39)") (class "Default")
      (node (ref "$$PCB100") (pin "39") (pinfunction "39/GPIO0-27_VREF_39") (pintype "bidirectional"))
    )
    (net (code "278") (name "unconnected-($$PCB100-41{slash}GPIO28-45_VREF-Pad41)") (class "Default")
      (node (ref "$$PCB100") (pin "41") (pinfunction "41/GPIO28-45_VREF_41") (pintype "bidirectional"))
    )
    (net (code "279") (name "unconnected-($$PCB100-43{slash}GND-Pad43)") (class "Default")
      (node (ref "$$PCB100") (pin "43") (pinfunction "43/GND_43") (pintype "bidirectional"))
    )
    (net (code "280") (name "unconnected-($$PCB100-44{slash}GND-Pad44)") (class "Default")
      (node (ref "$$PCB100") (pin "44") (pinfunction "44/GND_44") (pintype "bidirectional"))
    )
    (net (code "281") (name "unconnected-($$PCB100-45{slash}GPIO12-Pad45)") (class "Default")
      (node (ref "$$PCB100") (pin "45") (pinfunction "45/GPIO12_45") (pintype "bidirectional"))
    )
    (net (code "282") (name "unconnected-($$PCB100-47{slash}GPIO13-Pad47)") (class "Default")
      (node (ref "$$PCB100") (pin "47") (pinfunction "47/GPIO13_47") (pintype "bidirectional"))
    )
    (net (code "283") (name "unconnected-($$PCB100-49{slash}GND-Pad49)") (class "Default")
      (node (ref "$$PCB100") (pin "49") (pinfunction "49/GND_49") (pintype "bidirectional"))
    )
    (net (code "284") (name "unconnected-($$PCB100-50{slash}GND-Pad50)") (class "Default")
      (node (ref "$$PCB100") (pin "50") (pinfunction "50/GND_50") (pintype "bidirectional"))
    )
    (net (code "285") (name "unconnected-($$PCB100-51{slash}GPIO14-Pad51)") (class "Default")
      (node (ref "$$PCB100") (pin "51") (pinfunction "51/GPIO14_51") (pintype "bidirectional"))
    )
    (net (code "286") (name "unconnected-($$PCB100-53{slash}GPIO15-Pad53)") (class "Default")
      (node (ref "$$PCB100") (pin "53") (pinfunction "53/GPIO15_53") (pintype "bidirectional"))
    )
    (net (code "287") (name "unconnected-($$PCB100-55{slash}GND-Pad55)") (class "Default")
      (node (ref "$$PCB100") (pin "55") (pinfunction "55/GND_55") (pintype "bidirectional"))
    )
    (net (code "288") (name "unconnected-($$PCB100-56{slash}GND-Pad56)") (class "Default")
      (node (ref "$$PCB100") (pin "56") (pinfunction "56/GND_56") (pintype "bidirectional"))
    )
    (net (code "289") (name "unconnected-($$PCB100-57{slash}GPIO16-Pad57)") (class "Default")
      (node (ref "$$PCB100") (pin "57") (pinfunction "57/GPIO16_57") (pintype "bidirectional"))
    )
    (net (code "290") (name "unconnected-($$PCB100-59{slash}GPIO17-Pad59)") (class "Default")
      (node (ref "$$PCB100") (pin "59") (pinfunction "59/GPIO17_59") (pintype "bidirectional"))
    )
    (net (code "291") (name "unconnected-($$PCB100-61{slash}GND-Pad61)") (class "Default")
      (node (ref "$$PCB100") (pin "61") (pinfunction "61/GND_61") (pintype "bidirectional"))
    )
    (net (code "292") (name "unconnected-($$PCB100-62{slash}GND-Pad62)") (class "Default")
      (node (ref "$$PCB100") (pin "62") (pinfunction "62/GND_62") (pintype "bidirectional"))
    )
    (net (code "293") (name "unconnected-($$PCB100-63{slash}GPIO18-Pad63)") (class "Default")
      (node (ref "$$PCB100") (pin "63") (pinfunction "63/GPIO18_63") (pintype "bidirectional"))
    )
    (net (code "294") (name "unconnected-($$PCB100-65{slash}GPIO19-Pad65)") (class "Default")
      (node (ref "$$PCB100") (pin "65") (pinfunction "65/GPIO19_65") (pintype "bidirectional"))
    )
    (net (code "295") (name "unconnected-($$PCB100-67{slash}GND-Pad67)") (class "Default")
      (node (ref "$$PCB100") (pin "67") (pinfunction "67/GND_67") (pintype "bidirectional"))
    )
    (net (code "296") (name "unconnected-($$PCB100-68{slash}GND-Pad68)") (class "Default")
      (node (ref "$$PCB100") (pin "68") (pinfunction "68/GND_68") (pintype "bidirectional"))
    )
    (net (code "297") (name "unconnected-($$PCB100-73{slash}GND-Pad73)") (class "Default")
      (node (ref "$$PCB100") (pin "73") (pinfunction "73/GND_73") (pintype "bidirectional"))
    )
    (net (code "298") (name "unconnected-($$PCB100-74{slash}GND-Pad74)") (class "Default")
      (node (ref "$$PCB100") (pin "74") (pinfunction "74/GND_74") (pintype "bidirectional"))
    )
    (net (code "299") (name "unconnected-($$PCB100-79{slash}GND-Pad79)") (class "Default")
      (node (ref "$$PCB100") (pin "79") (pinfunction "79/GND_79") (pintype "bidirectional"))
    )
    (net (code "300") (name "unconnected-($$PCB100-80{slash}GND-Pad80)") (class "Default")
      (node (ref "$$PCB100") (pin "80") (pinfunction "80/GND_80") (pintype "bidirectional"))
    )
    (net (code "301") (name "unconnected-($$PCB100-85{slash}GND-Pad85)") (class "Default")
      (node (ref "$$PCB100") (pin "85") (pinfunction "85/GND_85") (pintype "bidirectional"))
    )
    (net (code "302") (name "unconnected-($$PCB100-86{slash}GND-Pad86)") (class "Default")
      (node (ref "$$PCB100") (pin "86") (pinfunction "86/GND_86") (pintype "bidirectional"))
    )
    (net (code "303") (name "unconnected-($$PCB100-90{slash}GPIO47_1V8-Pad90)") (class "Default")
      (node (ref "$$PCB100") (pin "90") (pinfunction "90/GPIO47_1V8_90") (pintype "bidirectional"))
    )
    (net (code "304") (name "unconnected-($$PCB100-91{slash}GND-Pad91)") (class "Default")
      (node (ref "$$PCB100") (pin "91") (pinfunction "91/GND_91") (pintype "bidirectional"))
    )
    (net (code "305") (name "unconnected-($$PCB100-92{slash}GND-Pad92)") (class "Default")
      (node (ref "$$PCB100") (pin "92") (pinfunction "92/GND_92") (pintype "bidirectional"))
    )
    (net (code "306") (name "unconnected-($$PCB100-93{slash}DSI0_DN1*-Pad93)") (class "Default")
      (node (ref "$$PCB100") (pin "93") (pinfunction "93/DSI0_DN1*_93") (pintype "bidirectional"))
    )
    (net (code "307") (name "unconnected-($$PCB100-94{slash}DSI1_DP0*-Pad94)") (class "Default")
      (node (ref "$$PCB100") (pin "94") (pinfunction "94/DSI1_DP0*_94") (pintype "bidirectional"))
    )
    (net (code "308") (name "unconnected-($$PCB100-95{slash}DSI0_DP1*-Pad95)") (class "Default")
      (node (ref "$$PCB100") (pin "95") (pinfunction "95/DSI0_DP1*_95") (pintype "bidirectional"))
    )
    (net (code "309") (name "unconnected-($$PCB100-96{slash}DSI1_DN0*-Pad96)") (class "Default")
      (node (ref "$$PCB100") (pin "96") (pinfunction "96/DSI1_DN0*_96") (pintype "bidirectional"))
    )
    (net (code "310") (name "unconnected-($$PCB100-97{slash}GND-Pad97)") (class "Default")
      (node (ref "$$PCB100") (pin "97") (pinfunction "97/GND_97") (pintype "bidirectional"))
    )
    (net (code "311") (name "unconnected-($$PCB100-98{slash}GND-Pad98)") (class "Default")
      (node (ref "$$PCB100") (pin "98") (pinfunction "98/GND_98") (pintype "bidirectional"))
    )
    (net (code "312") (name "unconnected-($$PCB100-99{slash}DSI0_DN0*-Pad99)") (class "Default")
      (node (ref "$$PCB100") (pin "99") (pinfunction "99/DSI0_DN0*_99") (pintype "bidirectional"))
    )
    (net (code "313") (name "unconnected-($$PCB100-100{slash}DSI1CP*-Pad100)") (class "Default")
      (node (ref "$$PCB100") (pin "100") (pinfunction "100/DSI1CP*_100") (pintype "bidirectional"))
    )
    (net (code "314") (name "unconnected-($$PCB100-101{slash}DSI0_DP0*-Pad101)") (class "Default")
      (node (ref "$$PCB100") (pin "101") (pinfunction "101/DSI0_DP0*_101") (pintype "bidirectional"))
    )
    (net (code "315") (name "unconnected-($$PCB100-102{slash}DSI1CN*-Pad102)") (class "Default")
      (node (ref "$$PCB100") (pin "102") (pinfunction "102/DSI1CN*_102") (pintype "bidirectional"))
    )
    (net (code "316") (name "unconnected-($$PCB100-103{slash}GND-Pad103)") (class "Default")
      (node (ref "$$PCB100") (pin "103") (pinfunction "103/GND_103") (pintype "bidirectional"))
    )
    (net (code "317") (name "unconnected-($$PCB100-104{slash}GND-Pad104)") (class "Default")
      (node (ref "$$PCB100") (pin "104") (pinfunction "104/GND_104") (pintype "bidirectional"))
    )
    (net (code "318") (name "unconnected-($$PCB100-105{slash}DSI0_CN*-Pad105)") (class "Default")
      (node (ref "$$PCB100") (pin "105") (pinfunction "105/DSI0_CN*_105") (pintype "bidirectional"))
    )
    (net (code "319") (name "unconnected-($$PCB100-106{slash}DSI1_DP3*-Pad106)") (class "Default")
      (node (ref "$$PCB100") (pin "106") (pinfunction "106/DSI1_DP3*_106") (pintype "bidirectional"))
    )
    (net (code "320") (name "unconnected-($$PCB100-107{slash}DSI0_CP*-Pad107)") (class "Default")
      (node (ref "$$PCB100") (pin "107") (pinfunction "107/DSI0_CP*_107") (pintype "bidirectional"))
    )
    (net (code "321") (name "unconnected-($$PCB100-108{slash}DSI1_DN3*-Pad108)") (class "Default")
      (node (ref "$$PCB100") (pin "108") (pinfunction "108/DSI1_DN3*_108") (pintype "bidirectional"))
    )
    (net (code "322") (name "unconnected-($$PCB100-109{slash}GND-Pad109)") (class "Default")
      (node (ref "$$PCB100") (pin "109") (pinfunction "109/GND_109") (pintype "bidirectional"))
    )
    (net (code "323") (name "unconnected-($$PCB100-110{slash}GND-Pad110)") (class "Default")
      (node (ref "$$PCB100") (pin "110") (pinfunction "110/GND_110") (pintype "bidirectional"))
    )
    (net (code "324") (name "unconnected-($$PCB100-111{slash}HDMI_CK_N*-Pad111)") (class "Default")
      (node (ref "$$PCB100") (pin "111") (pinfunction "111/HDMI_CK_N*_111") (pintype "bidirectional"))
    )
    (net (code "325") (name "unconnected-($$PCB100-112{slash}DSI1_DP2*-Pad112)") (class "Default")
      (node (ref "$$PCB100") (pin "112") (pinfunction "112/DSI1_DP2*_112") (pintype "bidirectional"))
    )
    (net (code "326") (name "unconnected-($$PCB100-113{slash}HDMI_CK_P*-Pad113)") (class "Default")
      (node (ref "$$PCB100") (pin "113") (pinfunction "113/HDMI_CK_P*_113") (pintype "bidirectional"))
    )
    (net (code "327") (name "unconnected-($$PCB100-114{slash}DSI1_DN2*-Pad114)") (class "Default")
      (node (ref "$$PCB100") (pin "114") (pinfunction "114/DSI1_DN2*_114") (pintype "bidirectional"))
    )
    (net (code "328") (name "unconnected-($$PCB100-115{slash}GND-Pad115)") (class "Default")
      (node (ref "$$PCB100") (pin "115") (pinfunction "115/GND_115") (pintype "bidirectional"))
    )
    (net (code "329") (name "unconnected-($$PCB100-116{slash}GND-Pad116)") (class "Default")
      (node (ref "$$PCB100") (pin "116") (pinfunction "116/GND_116") (pintype "bidirectional"))
    )
    (net (code "330") (name "unconnected-($$PCB100-117{slash}HDMI_D0_N*-Pad117)") (class "Default")
      (node (ref "$$PCB100") (pin "117") (pinfunction "117/HDMI_D0_N*_117") (pintype "bidirectional"))
    )
    (net (code "331") (name "unconnected-($$PCB100-118{slash}DSI1_DP1*-Pad118)") (class "Default")
      (node (ref "$$PCB100") (pin "118") (pinfunction "118/DSI1_DP1*_118") (pintype "bidirectional"))
    )
    (net (code "332") (name "unconnected-($$PCB100-119{slash}HDMI_D0_P*-Pad119)") (class "Default")
      (node (ref "$$PCB100") (pin "119") (pinfunction "119/HDMI_D0_P*_119") (pintype "bidirectional"))
    )
    (net (code "333") (name "unconnected-($$PCB100-120{slash}DSI1_DN1*-Pad120)") (class "Default")
      (node (ref "$$PCB100") (pin "120") (pinfunction "120/DSI1_DN1*_120") (pintype "bidirectional"))
    )
    (net (code "334") (name "unconnected-($$PCB100-121{slash}GND-Pad121)") (class "Default")
      (node (ref "$$PCB100") (pin "121") (pinfunction "121/GND_121") (pintype "bidirectional"))
    )
    (net (code "335") (name "unconnected-($$PCB100-122{slash}GND-Pad122)") (class "Default")
      (node (ref "$$PCB100") (pin "122") (pinfunction "122/GND_122") (pintype "bidirectional"))
    )
    (net (code "336") (name "unconnected-($$PCB100-123{slash}HDMI_D1_N*-Pad123)") (class "Default")
      (node (ref "$$PCB100") (pin "123") (pinfunction "123/HDMI_D1_N*_123") (pintype "bidirectional"))
    )
    (net (code "337") (name "unconnected-($$PCB100-124{slash}NC-Pad124)") (class "Default")
      (node (ref "$$PCB100") (pin "124") (pinfunction "124/NC_124") (pintype "bidirectional"))
    )
    (net (code "338") (name "unconnected-($$PCB100-125{slash}HDMI_D1_P*-Pad125)") (class "Default")
      (node (ref "$$PCB100") (pin "125") (pinfunction "125/HDMI_D1_P*_125") (pintype "bidirectional"))
    )
    (net (code "339") (name "unconnected-($$PCB100-126{slash}NC-Pad126)") (class "Default")
      (node (ref "$$PCB100") (pin "126") (pinfunction "126/NC_126") (pintype "bidirectional"))
    )
    (net (code "340") (name "unconnected-($$PCB100-127{slash}GND-Pad127)") (class "Default")
      (node (ref "$$PCB100") (pin "127") (pinfunction "127/GND_127") (pintype "bidirectional"))
    )
    (net (code "341") (name "unconnected-($$PCB100-128{slash}NC-Pad128)") (class "Default")
      (node (ref "$$PCB100") (pin "128") (pinfunction "128/NC_128") (pintype "bidirectional"))
    )
    (net (code "342") (name "unconnected-($$PCB100-129{slash}HDMI_D2_N*-Pad129)") (class "Default")
      (node (ref "$$PCB100") (pin "129") (pinfunction "129/HDMI_D2_N*_129") (pintype "bidirectional"))
    )
    (net (code "343") (name "unconnected-($$PCB100-130{slash}NC-Pad130)") (class "Default")
      (node (ref "$$PCB100") (pin "130") (pinfunction "130/NC_130") (pintype "bidirectional"))
    )
    (net (code "344") (name "unconnected-($$PCB100-131{slash}HDMI_D2_P*-Pad131)") (class "Default")
      (node (ref "$$PCB100") (pin "131") (pinfunction "131/HDMI_D2_P*_131") (pintype "bidirectional"))
    )
    (net (code "345") (name "unconnected-($$PCB100-132{slash}NC-Pad132)") (class "Default")
      (node (ref "$$PCB100") (pin "132") (pinfunction "132/NC_132") (pintype "bidirectional"))
    )
    (net (code "346") (name "unconnected-($$PCB100-133{slash}GND-Pad133)") (class "Default")
      (node (ref "$$PCB100") (pin "133") (pinfunction "133/GND_133") (pintype "bidirectional"))
    )
    (net (code "347") (name "unconnected-($$PCB100-135{slash}CAM1_DP3*-Pad135)") (class "Default")
      (node (ref "$$PCB100") (pin "135") (pinfunction "135/CAM1_DP3*_135") (pintype "bidirectional"))
    )
    (net (code "348") (name "unconnected-($$PCB100-136{slash}CAM0_DP0*-Pad136)") (class "Default")
      (node (ref "$$PCB100") (pin "136") (pinfunction "136/CAM0_DP0*_136") (pintype "bidirectional"))
    )
    (net (code "349") (name "unconnected-($$PCB100-137{slash}CAM1_DN3*-Pad137)") (class "Default")
      (node (ref "$$PCB100") (pin "137") (pinfunction "137/CAM1_DN3*_137") (pintype "bidirectional"))
    )
    (net (code "350") (name "unconnected-($$PCB100-138{slash}CAM0_DN0*-Pad138)") (class "Default")
      (node (ref "$$PCB100") (pin "138") (pinfunction "138/CAM0_DN0*_138") (pintype "bidirectional"))
    )
    (net (code "351") (name "unconnected-($$PCB100-139{slash}GND-Pad139)") (class "Default")
      (node (ref "$$PCB100") (pin "139") (pinfunction "139/GND_139") (pintype "bidirectional"))
    )
    (net (code "352") (name "unconnected-($$PCB100-140{slash}GND-Pad140)") (class "Default")
      (node (ref "$$PCB100") (pin "140") (pinfunction "140/GND_140") (pintype "bidirectional"))
    )
    (net (code "353") (name "unconnected-($$PCB100-141{slash}CAM1_DP2*-Pad141)") (class "Default")
      (node (ref "$$PCB100") (pin "141") (pinfunction "141/CAM1_DP2*_141") (pintype "bidirectional"))
    )
    (net (code "354") (name "unconnected-($$PCB100-142{slash}CAM0_CP*-Pad142)") (class "Default")
      (node (ref "$$PCB100") (pin "142") (pinfunction "142/CAM0_CP*_142") (pintype "bidirectional"))
    )
    (net (code "355") (name "unconnected-($$PCB100-143{slash}CAM1_DN2*-Pad143)") (class "Default")
      (node (ref "$$PCB100") (pin "143") (pinfunction "143/CAM1_DN2*_143") (pintype "bidirectional"))
    )
    (net (code "356") (name "unconnected-($$PCB100-144{slash}CAM0_CN*-Pad144)") (class "Default")
      (node (ref "$$PCB100") (pin "144") (pinfunction "144/CAM0_CN*_144") (pintype "bidirectional"))
    )
    (net (code "357") (name "unconnected-($$PCB100-145{slash}GND-Pad145)") (class "Default")
      (node (ref "$$PCB100") (pin "145") (pinfunction "145/GND_145") (pintype "bidirectional"))
    )
    (net (code "358") (name "unconnected-($$PCB100-146{slash}GND-Pad146)") (class "Default")
      (node (ref "$$PCB100") (pin "146") (pinfunction "146/GND_146") (pintype "bidirectional"))
    )
    (net (code "359") (name "unconnected-($$PCB100-147{slash}CAM1_CP*-Pad147)") (class "Default")
      (node (ref "$$PCB100") (pin "147") (pinfunction "147/CAM1_CP*_147") (pintype "bidirectional"))
    )
    (net (code "360") (name "unconnected-($$PCB100-148{slash}CAM0_DP1*-Pad148)") (class "Default")
      (node (ref "$$PCB100") (pin "148") (pinfunction "148/CAM0_DP1*_148") (pintype "bidirectional"))
    )
    (net (code "361") (name "unconnected-($$PCB100-149{slash}CAM1_CN*-Pad149)") (class "Default")
      (node (ref "$$PCB100") (pin "149") (pinfunction "149/CAM1_CN*_149") (pintype "bidirectional"))
    )
    (net (code "362") (name "unconnected-($$PCB100-150{slash}CAM0_DN1*-Pad150)") (class "Default")
      (node (ref "$$PCB100") (pin "150") (pinfunction "150/CAM0_DN1*_150") (pintype "bidirectional"))
    )
    (net (code "363") (name "unconnected-($$PCB100-151{slash}GND-Pad151)") (class "Default")
      (node (ref "$$PCB100") (pin "151") (pinfunction "151/GND_151") (pintype "bidirectional"))
    )
    (net (code "364") (name "unconnected-($$PCB100-152{slash}GND-Pad152)") (class "Default")
      (node (ref "$$PCB100") (pin "152") (pinfunction "152/GND_152") (pintype "bidirectional"))
    )
    (net (code "365") (name "unconnected-($$PCB100-153{slash}CAM1_DP1*-Pad153)") (class "Default")
      (node (ref "$$PCB100") (pin "153") (pinfunction "153/CAM1_DP1*_153") (pintype "bidirectional"))
    )
    (net (code "366") (name "unconnected-($$PCB100-154{slash}NC-Pad154)") (class "Default")
      (node (ref "$$PCB100") (pin "154") (pinfunction "154/NC_154") (pintype "bidirectional"))
    )
    (net (code "367") (name "unconnected-($$PCB100-155{slash}CAM1_DN1*-Pad155)") (class "Default")
      (node (ref "$$PCB100") (pin "155") (pinfunction "155/CAM1_DN1*_155") (pintype "bidirectional"))
    )
    (net (code "368") (name "unconnected-($$PCB100-156{slash}NC-Pad156)") (class "Default")
      (node (ref "$$PCB100") (pin "156") (pinfunction "156/NC_156") (pintype "bidirectional"))
    )
    (net (code "369") (name "unconnected-($$PCB100-157{slash}GND-Pad157)") (class "Default")
      (node (ref "$$PCB100") (pin "157") (pinfunction "157/GND_157") (pintype "bidirectional"))
    )
    (net (code "370") (name "unconnected-($$PCB100-158{slash}NC-Pad158)") (class "Default")
      (node (ref "$$PCB100") (pin "158") (pinfunction "158/NC_158") (pintype "bidirectional"))
    )
    (net (code "371") (name "unconnected-($$PCB100-159{slash}CAM1_DP0*-Pad159)") (class "Default")
      (node (ref "$$PCB100") (pin "159") (pinfunction "159/CAM1_DP0*_159") (pintype "bidirectional"))
    )
    (net (code "372") (name "unconnected-($$PCB100-160{slash}NC-Pad160)") (class "Default")
      (node (ref "$$PCB100") (pin "160") (pinfunction "160/NC_160") (pintype "bidirectional"))
    )
    (net (code "373") (name "unconnected-($$PCB100-161{slash}CAM1_DN0*-Pad161)") (class "Default")
      (node (ref "$$PCB100") (pin "161") (pinfunction "161/CAM1_DN0*_161") (pintype "bidirectional"))
    )
    (net (code "374") (name "unconnected-($$PCB100-162{slash}NC-Pad162)") (class "Default")
      (node (ref "$$PCB100") (pin "162") (pinfunction "162/NC_162") (pintype "bidirectional"))
    )
    (net (code "375") (name "unconnected-($$PCB100-163{slash}GND-Pad163)") (class "Default")
      (node (ref "$$PCB100") (pin "163") (pinfunction "163/GND_163") (pintype "bidirectional"))
    )
    (net (code "376") (name "unconnected-($$PCB100-164{slash}GND-Pad164)") (class "Default")
      (node (ref "$$PCB100") (pin "164") (pinfunction "164/GND_164") (pintype "bidirectional"))
    )
    (net (code "377") (name "unconnected-($$PCB100-166{slash}TVDAC-Pad166)") (class "Default")
      (node (ref "$$PCB100") (pin "166") (pinfunction "166/TVDAC_166") (pintype "bidirectional"))
    )
    (net (code "378") (name "unconnected-($$PCB100-169{slash}GND-Pad169)") (class "Default")
      (node (ref "$$PCB100") (pin "169") (pinfunction "169/GND_169") (pintype "bidirectional"))
    )
    (net (code "379") (name "unconnected-($$PCB100-170{slash}GND-Pad170)") (class "Default")
      (node (ref "$$PCB100") (pin "170") (pinfunction "170/GND_170") (pintype "bidirectional"))
    )
    (net (code "380") (name "unconnected-($$PCB100-171{slash}HDMI_CEC-Pad171)") (class "Default")
      (node (ref "$$PCB100") (pin "171") (pinfunction "171/HDMI_CEC_171") (pintype "bidirectional"))
    )
    (net (code "381") (name "unconnected-($$PCB100-172{slash}VC_TRST_N-Pad172)") (class "Default")
      (node (ref "$$PCB100") (pin "172") (pinfunction "172/VC_TRST_N_172") (pintype "bidirectional"))
    )
    (net (code "382") (name "unconnected-($$PCB100-173{slash}HDMI_SDA-Pad173)") (class "Default")
      (node (ref "$$PCB100") (pin "173") (pinfunction "173/HDMI_SDA_173") (pintype "bidirectional"))
    )
    (net (code "383") (name "unconnected-($$PCB100-174{slash}VC_TDI-Pad174)") (class "Default")
      (node (ref "$$PCB100") (pin "174") (pinfunction "174/VC_TDI_174") (pintype "bidirectional"))
    )
    (net (code "384") (name "unconnected-($$PCB100-175{slash}HDMI_SCL-Pad175)") (class "Default")
      (node (ref "$$PCB100") (pin "175") (pinfunction "175/HDMI_SCL_175") (pintype "bidirectional"))
    )
    (net (code "385") (name "unconnected-($$PCB100-176{slash}VC_TMS-Pad176)") (class "Default")
      (node (ref "$$PCB100") (pin "176") (pinfunction "176/VC_TMS_176") (pintype "bidirectional"))
    )
    (net (code "386") (name "unconnected-($$PCB100-177{slash}RUN-Pad177)") (class "Default")
      (node (ref "$$PCB100") (pin "177") (pinfunction "177/RUN_177") (pintype "bidirectional"))
    )
    (net (code "387") (name "unconnected-($$PCB100-178{slash}VC_TDO-Pad178)") (class "Default")
      (node (ref "$$PCB100") (pin "178") (pinfunction "178/VC_TDO_178") (pintype "bidirectional"))
    )
    (net (code "388") (name "unconnected-($$PCB100-179{slash}VDD_CORE-Pad179)") (class "Default")
      (node (ref "$$PCB100") (pin "179") (pinfunction "179/VDD_CORE_179") (pintype "bidirectional"))
    )
    (net (code "389") (name "unconnected-($$PCB100-180{slash}VC_TCK-Pad180)") (class "Default")
      (node (ref "$$PCB100") (pin "180") (pinfunction "180/VC_TCK_180") (pintype "bidirectional"))
    )
    (net (code "390") (name "unconnected-($$PCB100-181{slash}GND-Pad181)") (class "Default")
      (node (ref "$$PCB100") (pin "181") (pinfunction "181/GND_181") (pintype "bidirectional"))
    )
    (net (code "391") (name "unconnected-($$PCB100-182{slash}GND-Pad182)") (class "Default")
      (node (ref "$$PCB100") (pin "182") (pinfunction "182/GND_182") (pintype "bidirectional"))
    )
    (net (code "392") (name "unconnected-($$PCB100-187{slash}GND-Pad187)") (class "Default")
      (node (ref "$$PCB100") (pin "187") (pinfunction "187/GND_187") (pintype "bidirectional"))
    )
    (net (code "393") (name "unconnected-($$PCB100-188{slash}GND-Pad188)") (class "Default")
      (node (ref "$$PCB100") (pin "188") (pinfunction "188/GND_188") (pintype "bidirectional"))
    )
    (net (code "394") (name "unconnected-($$PCB100-195{slash}GND-Pad195)") (class "Default")
      (node (ref "$$PCB100") (pin "195") (pinfunction "195/GND_195") (pintype "bidirectional"))
    )
    (net (code "395") (name "unconnected-($$PCB100-196{slash}GND-Pad196)") (class "Default")
      (node (ref "$$PCB100") (pin "196") (pinfunction "196/GND_196") (pintype "bidirectional"))
    )
    (net (code "396") (name "unconnected-($$U$100-NC1-Pad5)") (class "Default")
      (node (ref "$$U$100") (pin "5") (pinfunction "NC1_5") (pintype "bidirectional"))
    )
    (net (code "397") (name "unconnected-($$U$100-NC2-Pad11)") (class "Default")
      (node (ref "$$U$100") (pin "11") (pinfunction "NC2_11") (pintype "bidirectional"))
    )
    (net (code "398") (name "unconnected-($$U$101-ADJ-Pad4)") (class "Default")
      (node (ref "$$U$101") (pin "4") (pinfunction "ADJ_4") (pintype "bidirectional"))
    )
    (net (code "399") (name "unconnected-(JP1-Pad3)") (class "Default")
      (node (ref "JP1") (pin "3") (pinfunction "3_3") (pintype "passive"))
    )
    (net (code "400") (name "unconnected-(TFT1-DE-Pad14)") (class "Default")
      (node (ref "TFT1") (pin "14") (pinfunction "DE_14") (pintype "bidirectional"))
    )
    (net (code "401") (name "unconnected-(TFT1-DOTCLK-Pad13)") (class "Default")
      (node (ref "TFT1") (pin "13") (pinfunction "DOTCLK_13") (pintype "bidirectional"))
    )
    (net (code "402") (name "unconnected-(TFT1-HSYNC-Pad12)") (class "Default")
      (node (ref "TFT1") (pin "12") (pinfunction "HSYNC_12") (pintype "bidirectional"))
    )
    (net (code "403") (name "unconnected-(TFT1-TE-Pad39)") (class "Default")
      (node (ref "TFT1") (pin "39") (pinfunction "TE_39") (pintype "bidirectional"))
    )
    (net (code "404") (name "unconnected-(TFT1-VSYNC-Pad11)") (class "Default")
      (node (ref "TFT1") (pin "11") (pinfunction "VSYNC_11") (pintype "bidirectional"))
    )
    (net (code "405") (name "unconnected-(TFT1-{slash}RD-Pad35)") (class "Default")
      (node (ref "TFT1") (pin "35") (pinfunction "/RD_35") (pintype "bidirectional"))
    )
    (net (code "406") (name "unconnected-(UTSC-IN0{slash}GPIO-0-Pad8)") (class "Default")
      (node (ref "UTSC") (pin "8") (pinfunction "IN0/GPIO-0_8") (pintype "bidirectional"))
    )
    (net (code "407") (name "unconnected-(UTSC-IN3{slash}GPIO-3-Pad12)") (class "Default")
      (node (ref "UTSC") (pin "12") (pinfunction "IN3/GPIO-3_12") (pintype "bidirectional"))
    )
  )
)
